# Main_Board.net
KiCad netlist of a schematic drawn in Altium Designer
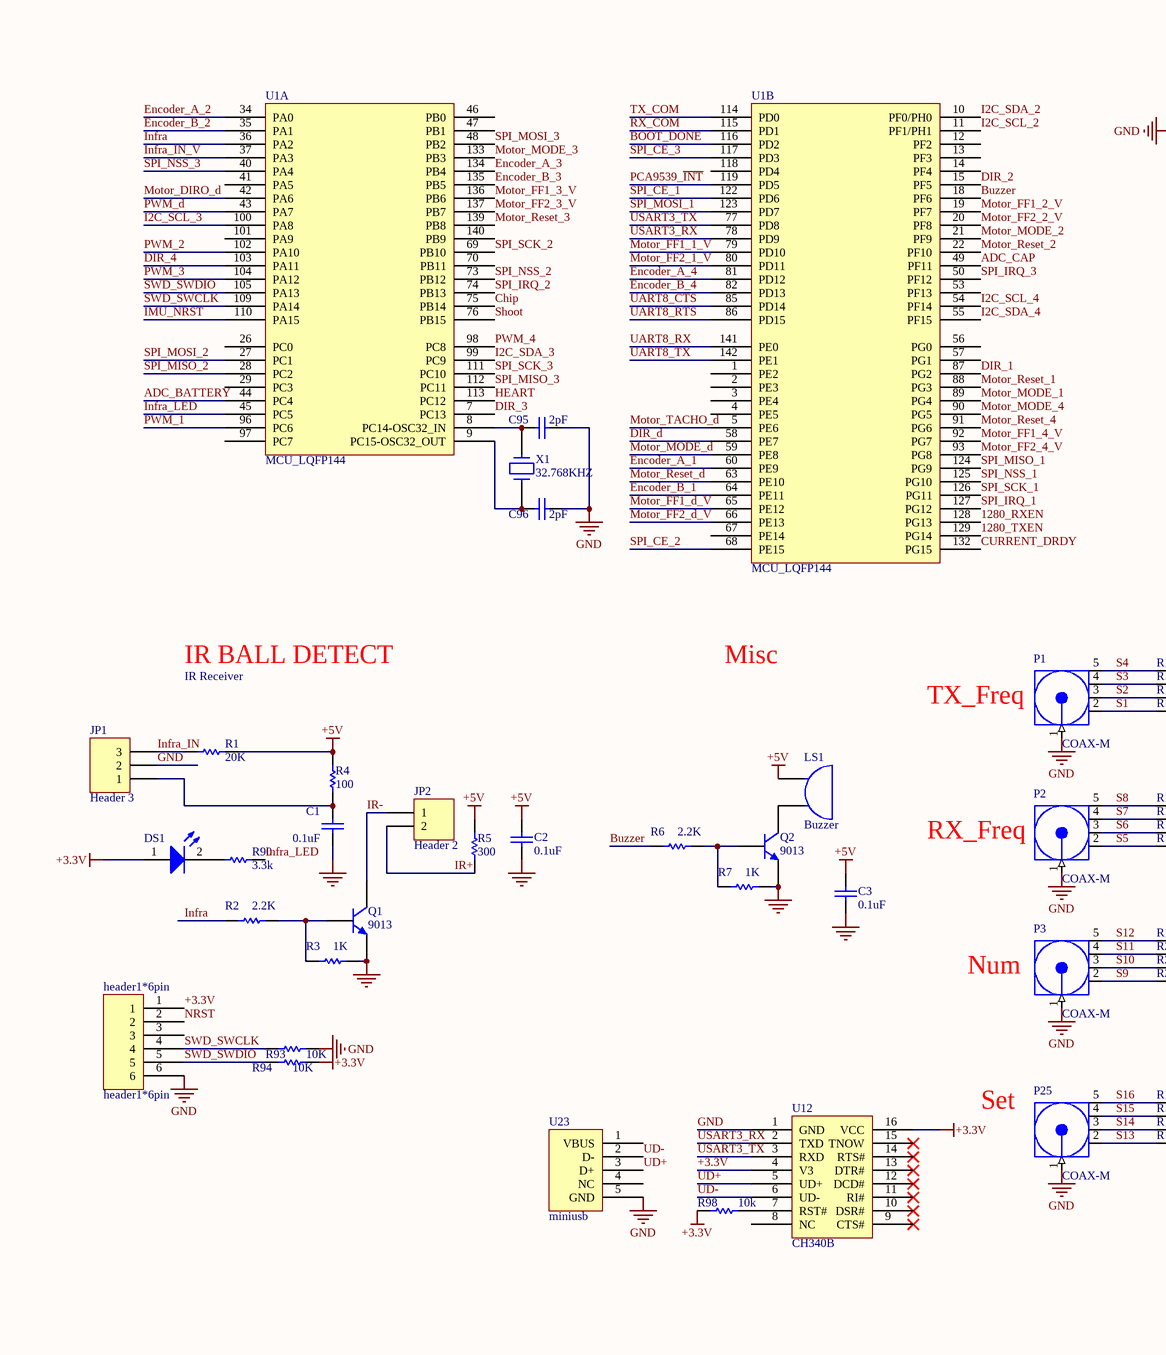
[diagram p0: Main_Board.SchDoc, left]
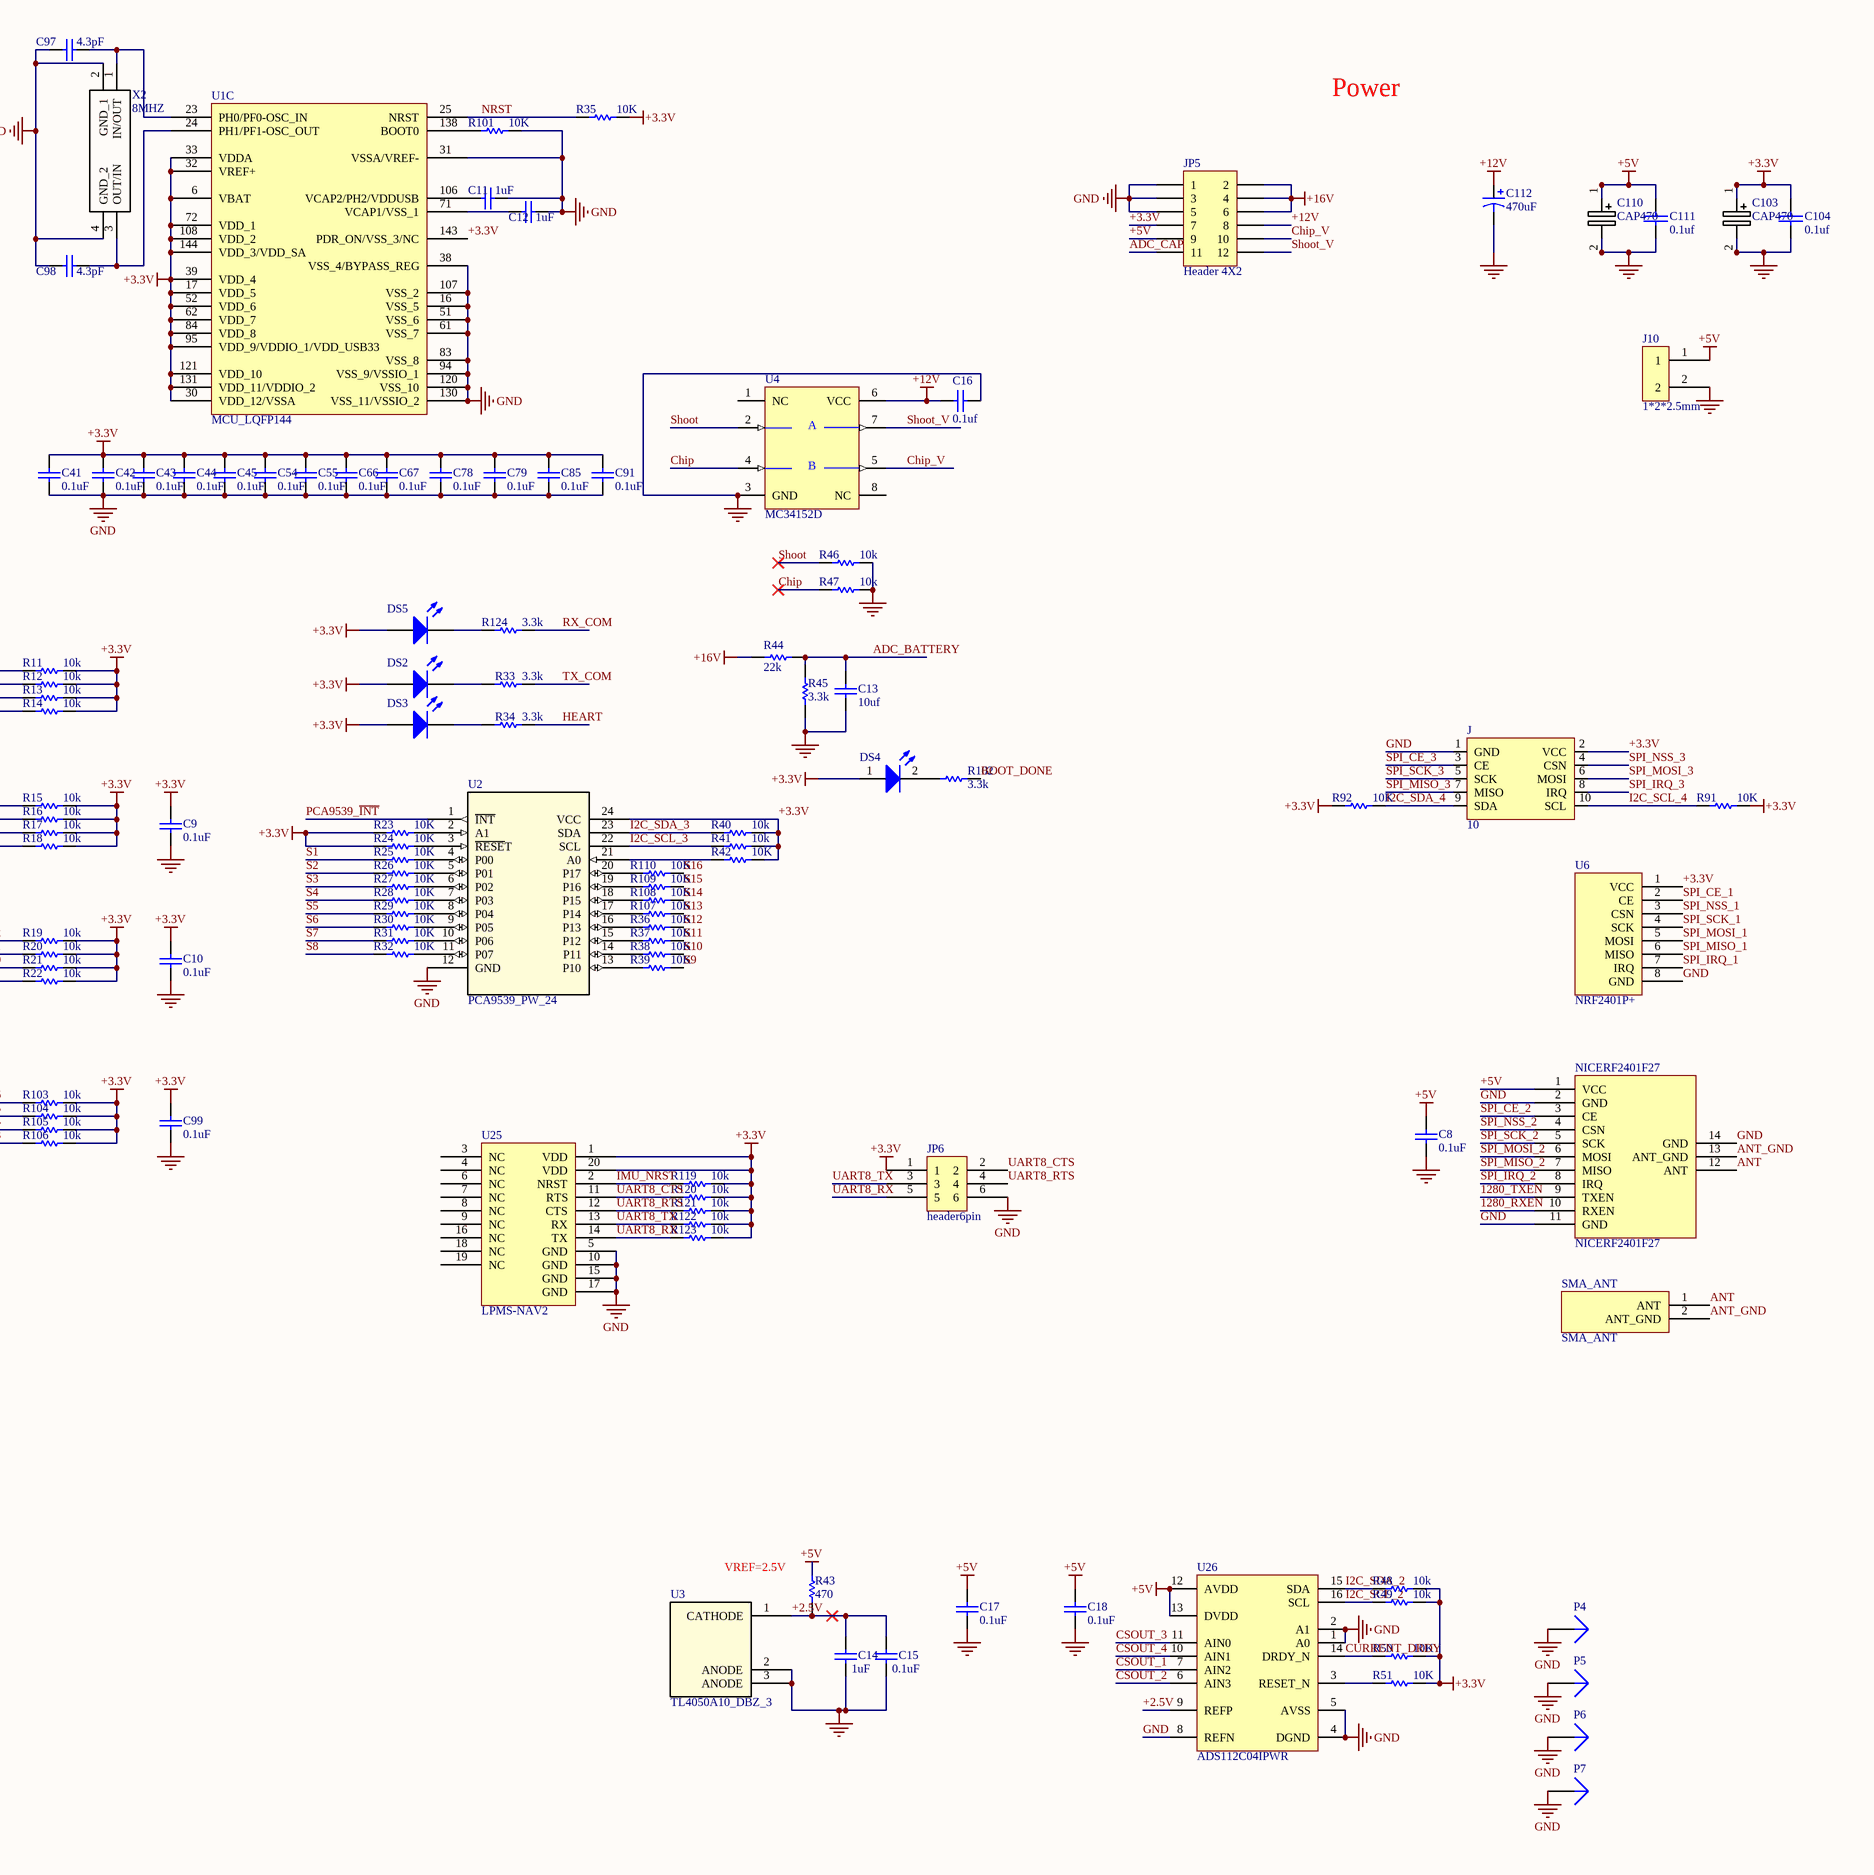
[diagram p1: Main_Board.SchDoc, right]

(export (version "E")
  (design (tool "Eeschema 10.0.6"))
  (components
    (comp (ref "C1")
      (value "0.1uF")
      (footprint "0805C")
      (description "Capacitor")
      (fields (field (name "Comment") "0.1uf") (field (name "PUBLISHER") "Altium Limited"))
      (libsource (lib "Miscellaneous Devices") (part "Cap"))
    )
    (comp (ref "C2")
      (value "0.1uF")
      (footprint "0805C")
      (description "Capacitor")
      (fields (field (name "Comment") "0.1uf") (field (name "PUBLISHER") "Altium Limited"))
      (libsource (lib "Miscellaneous Devices") (part "Cap"))
    )
    (comp (ref "C3")
      (value "0.1uF")
      (footprint "0805C")
      (description "Capacitor")
      (fields (field (name "Comment") "0.1uf") (field (name "PUBLISHER") "Altium Limited"))
      (libsource (lib "Miscellaneous Devices") (part "Cap"))
    )
    (comp (ref "C8")
      (value "0.1uF")
      (footprint "0805C")
      (description "Capacitor")
      (fields (field (name "PUBLISHER") "Altium Limited"))
      (libsource (lib "Miscellaneous Devices") (part "Cap"))
    )
    (comp (ref "C9")
      (value "0.1uF")
      (footprint "0805C")
      (description "Capacitor")
      (fields (field (name "Comment") "0.1uf") (field (name "PUBLISHER") "Altium Limited"))
      (libsource (lib "Miscellaneous Devices") (part "Cap"))
    )
    (comp (ref "C10")
      (value "0.1uF")
      (footprint "0805C")
      (description "Capacitor")
      (fields (field (name "Comment") "0.1uf") (field (name "PUBLISHER") "Altium Limited"))
      (libsource (lib "Miscellaneous Devices") (part "Cap"))
    )
    (comp (ref "C11")
      (value "1uF")
      (footprint "0805C")
      (description "Capacitor")
      (fields (field (name "Comment") "1uf") (field (name "PUBLISHER") "Altium Limited"))
      (libsource (lib "Miscellaneous Devices") (part "Cap"))
    )
    (comp (ref "C12")
      (value "1uF")
      (footprint "0805C")
      (description "Capacitor")
      (fields (field (name "Comment") "1uf") (field (name "PUBLISHER") "Altium Limited"))
      (libsource (lib "Miscellaneous Devices") (part "Cap"))
    )
    (comp (ref "C13")
      (value "10uf")
      (footprint "0805C")
      (description "Capacitor")
      (fields (field (name "PUBLISHER") "Altium Limited"))
      (libsource (lib "Miscellaneous Devices") (part "Cap"))
    )
    (comp (ref "C14")
      (value "1uF")
      (footprint "0805C")
      (description "Capacitor")
      (fields
        (field (name "MANUFACTURER") "Generic Components")
        (field (name "Comment") "1uf")
        (field (name "PUBLISHER") "Altium Hobart Technology Centre")
      )
      (libsource (lib "Miscellaneous Devices") (part "Cap"))
    )
    (comp (ref "C15")
      (value "0.1uF")
      (footprint "0805C")
      (description "Capacitor")
      (fields
        (field (name "MANUFACTURER") "Generic Components")
        (field (name "Comment") "0.1uf")
        (field (name "PUBLISHER") "Altium Hobart Technology Centre")
      )
      (libsource (lib "Miscellaneous Devices") (part "Cap"))
    )
    (comp (ref "C16")
      (value "0.1uf")
      (footprint "0805C")
      (description "Capacitor")
      (fields (field (name "PUBLISHER") "Altium Limited"))
      (libsource (lib "Miscellaneous Devices") (part "Cap"))
    )
    (comp (ref "C17")
      (value "0.1uF")
      (footprint "0805C")
      (description "Capacitor")
      (fields
        (field (name "MANUFACTURER") "Generic Components")
        (field (name "Comment") "0.1uf")
        (field (name "PUBLISHER") "Altium Hobart Technology Centre")
      )
      (libsource (lib "Miscellaneous Devices") (part "Cap"))
    )
    (comp (ref "C18")
      (value "0.1uF")
      (footprint "0805C")
      (description "Capacitor")
      (fields
        (field (name "MANUFACTURER") "Generic Components")
        (field (name "Comment") "0.1uf")
        (field (name "PUBLISHER") "Altium Hobart Technology Centre")
      )
      (libsource (lib "Miscellaneous Devices") (part "Cap"))
    )
    (comp (ref "C41")
      (value "0.1uF")
      (footprint "0805C")
      (description "Capacitor")
      (fields (field (name "PUBLISHER") "Altium Limited"))
      (libsource (lib "Miscellaneous Devices") (part "Cap"))
    )
    (comp (ref "C42")
      (value "0.1uF")
      (footprint "0805C")
      (description "Capacitor")
      (fields (field (name "Comment") "0.1uf") (field (name "PUBLISHER") "Altium Limited"))
      (libsource (lib "Miscellaneous Devices") (part "Cap"))
    )
    (comp (ref "C43")
      (value "0.1uF")
      (footprint "0805C")
      (description "Capacitor")
      (fields (field (name "Comment") "0.1uf") (field (name "PUBLISHER") "Altium Limited"))
      (libsource (lib "Miscellaneous Devices") (part "Cap"))
    )
    (comp (ref "C44")
      (value "0.1uF")
      (footprint "0805C")
      (description "Capacitor")
      (fields (field (name "Comment") "0.1uf") (field (name "PUBLISHER") "Altium Limited"))
      (libsource (lib "Miscellaneous Devices") (part "Cap"))
    )
    (comp (ref "C45")
      (value "0.1uF")
      (footprint "0805C")
      (description "Capacitor")
      (fields (field (name "Comment") "0.1uf") (field (name "PUBLISHER") "Altium Limited"))
      (libsource (lib "Miscellaneous Devices") (part "Cap"))
    )
    (comp (ref "C54")
      (value "0.1uF")
      (footprint "0805C")
      (description "Capacitor")
      (fields (field (name "Comment") "0.1uf") (field (name "PUBLISHER") "Altium Limited"))
      (libsource (lib "Miscellaneous Devices") (part "Cap"))
    )
    (comp (ref "C55")
      (value "0.1uF")
      (footprint "0805C")
      (description "Capacitor")
      (fields (field (name "Comment") "0.1uf") (field (name "PUBLISHER") "Altium Limited"))
      (libsource (lib "Miscellaneous Devices") (part "Cap"))
    )
    (comp (ref "C66")
      (value "0.1uF")
      (footprint "0805C")
      (description "Capacitor")
      (fields (field (name "Comment") "0.1uf") (field (name "PUBLISHER") "Altium Limited"))
      (libsource (lib "Miscellaneous Devices") (part "Cap"))
    )
    (comp (ref "C67")
      (value "0.1uF")
      (footprint "0805C")
      (description "Capacitor")
      (fields (field (name "Comment") "0.1uf") (field (name "PUBLISHER") "Altium Limited"))
      (libsource (lib "Miscellaneous Devices") (part "Cap"))
    )
    (comp (ref "C78")
      (value "0.1uF")
      (footprint "0805C")
      (description "Capacitor")
      (fields (field (name "Comment") "0.1uf") (field (name "PUBLISHER") "Altium Limited"))
      (libsource (lib "Miscellaneous Devices") (part "Cap"))
    )
    (comp (ref "C79")
      (value "0.1uF")
      (footprint "0805C")
      (description "Capacitor")
      (fields (field (name "Comment") "0.1uf") (field (name "PUBLISHER") "Altium Limited"))
      (libsource (lib "Miscellaneous Devices") (part "Cap"))
    )
    (comp (ref "C85")
      (value "0.1uF")
      (footprint "0805C")
      (description "Capacitor")
      (fields (field (name "Comment") "0.1uf") (field (name "PUBLISHER") "Altium Limited"))
      (libsource (lib "Miscellaneous Devices") (part "Cap"))
    )
    (comp (ref "C91")
      (value "0.1uF")
      (footprint "0805C")
      (description "Capacitor")
      (fields (field (name "Comment") "0.1uf") (field (name "PUBLISHER") "Altium Limited"))
      (libsource (lib "Miscellaneous Devices") (part "Cap"))
    )
    (comp (ref "C95")
      (value "2pF")
      (footprint "0805C")
      (description "Capacitor")
      (fields (field (name "Comment") "2pf") (field (name "PUBLISHER") "Altium Limited"))
      (libsource (lib "Miscellaneous Devices") (part "Cap"))
    )
    (comp (ref "C96")
      (value "2pF")
      (footprint "0805C")
      (description "Capacitor")
      (fields (field (name "Comment") "2pf") (field (name "PUBLISHER") "Altium Limited"))
      (libsource (lib "Miscellaneous Devices") (part "Cap"))
    )
    (comp (ref "C97")
      (value "4.3pF")
      (footprint "0805C")
      (description "Capacitor")
      (fields (field (name "Comment") "4.3pf") (field (name "PUBLISHER") "Altium Limited"))
      (libsource (lib "Miscellaneous Devices") (part "Cap"))
    )
    (comp (ref "C98")
      (value "4.3pF")
      (footprint "0805C")
      (description "Capacitor")
      (fields (field (name "Comment") "4.3pf") (field (name "PUBLISHER") "Altium Limited"))
      (libsource (lib "Miscellaneous Devices") (part "Cap"))
    )
    (comp (ref "C99")
      (value "0.1uF")
      (footprint "0805C")
      (description "Capacitor")
      (fields (field (name "PUBLISHER") "Altium Limited"))
      (libsource (lib "Miscellaneous Devices") (part "Cap"))
    )
    (comp (ref "C103")
      (value "CAP470")
      (footprint "Main_Board:CAPPM7360X200N")
      (description "470uF电容贴片")
      (fields
        (field (name "MANUFACTURER_PART_NUMBER") "T523H477M016APE0707280")
        (field (name "MOUSER PART NUMBER") "80-T523H477M16P070LR")
      )
      (libsource (lib "Main_Board") (part "T523H477M016APE0707280"))
    )
    (comp (ref "C104")
      (value "0.1uf")
      (footprint "0805C")
      (description "Capacitor")
      (libsource (lib "*") (part "CAP"))
    )
    (comp (ref "C110")
      (value "CAP470")
      (footprint "Main_Board:CAPPM7360X200N")
      (description "470uF电容贴片")
      (fields
        (field (name "MANUFACTURER_PART_NUMBER") "T523H477M016APE0707280")
        (field (name "MOUSER PART NUMBER") "80-T523H477M16P070LR")
      )
      (libsource (lib "Main_Board") (part "T523H477M016APE0707280"))
    )
    (comp (ref "C111")
      (value "0.1uf")
      (footprint "0805C")
      (description "Capacitor")
      (libsource (lib "*") (part "CAP"))
    )
    (comp (ref "C112")
      (value "470uF")
      (footprint "470uF")
      (description "Polarized Capacitor (Radial)")
      (fields (field (name "PUBLISHER") "Altium Limited"))
      (libsource (lib "Miscellaneous Devices") (part "Cap Pol1"))
    )
    (comp (ref "DS1")
      (value "LED2")
      (footprint "0805D")
      (description "Typical RED, GREEN, YELLOW, AMBER GaAs LED")
      (fields
        (field (name "MANUFACTURER") "Generic Components")
        (field (name "PUBLISHER") "Altium Hobart Technology Centre")
      )
      (libsource (lib "Miscellaneous Devices") (part "LED2"))
    )
    (comp (ref "DS2")
      (value "LED1")
      (footprint "0805D")
      (description "Typical RED, GREEN, YELLOW, AMBER GaAs LED")
      (fields (field (name "PUBLISHER") "Altium Limited"))
      (libsource (lib "Miscellaneous Devices") (part "LED1"))
    )
    (comp (ref "DS3")
      (value "LED2")
      (footprint "0805D")
      (description "Typical RED, GREEN, YELLOW, AMBER GaAs LED")
      (fields (field (name "PUBLISHER") "Altium Limited"))
      (libsource (lib "") (part "LED2_1"))
    )
    (comp (ref "DS4")
      (value "LED2")
      (footprint "0805D")
      (description "Typical RED, GREEN, YELLOW, AMBER GaAs LED")
      (fields
        (field (name "MANUFACTURER") "Generic Components")
        (field (name "PUBLISHER") "Altium Hobart Technology Centre")
      )
      (libsource (lib "Miscellaneous Devices") (part "LED2"))
    )
    (comp (ref "DS5")
      (value "LED1")
      (footprint "0805D")
      (description "Typical RED, GREEN, YELLOW, AMBER GaAs LED")
      (fields (field (name "PUBLISHER") "Altium Limited"))
      (libsource (lib "Miscellaneous Devices") (part "LED1"))
    )
    (comp (ref "header1*6pin")
      (value "header1*6pin")
      (footprint "1*6_2.5mm")
      (libsource (lib "Main_Board") (part "header1*6pin"))
    )
    (comp (ref "J") (value "10") (footprint "Main_Board:10") (libsource (lib "Main_Board") (part "10")))
    (comp (ref "J10")
      (value "1*2*2.5mm")
      (footprint "1*2_2.5mm")
      (libsource (lib "Main_Board") (part "1*2*2.5mm"))
    )
    (comp (ref "JP1")
      (value "Header 3")
      (footprint "SHDR3")
      (description "Header, 3-Pin")
      (fields (field (name "PUBLISHER") "Altium Limited"))
      (libsource (lib "Miscellaneous Connectors") (part "Header 3"))
    )
    (comp (ref "JP2")
      (value "Header 2")
      (footprint "SHDR2")
      (description "Header, 2-Pin")
      (fields (field (name "PUBLISHER") "Altium Limited"))
      (libsource (lib "Miscellaneous Connectors") (part "Header 2"))
    )
    (comp (ref "JP5")
      (value "Header 4X2")
      (footprint "2*6_2.5mm")
      (description "Header, 4-Pin, Dual row")
      (fields (field (name "PUBLISHER") "Altium Limited"))
      (libsource (lib "booster") (part "Header 6X2"))
    )
    (comp (ref "JP6")
      (value "header6pin")
      (footprint "2*3_2.5mm")
      (libsource (lib "Main_Board") (part "header6pin"))
    )
    (comp (ref "LS1")
      (value "Buzzer")
      (footprint "Buzzer")
      (fields (field (name "MANUFACTURER") "Generic Components"))
      (libsource (lib "Miscellaneous Devices") (part "Buzzer"))
    )
    (comp (ref "NICERF2401F27")
      (value "NICERF2401F27")
      (footprint "NICERF2401F27")
      (libsource (lib "Main_Board") (part "NICERF2401F27"))
    )
    (comp (ref "P1")
      (value "COAX-M")
      (footprint "A6RV-161RS")
      (description "RF Coaxial PCB Connector, MMCX; Thru-Hole, Vertical Mount Plug,  50 Ohm Impedance")
      (fields (field (name "PUBLISHER") "Altium Limited"))
      (libsource (lib "Miscellaneous Connectors") (part "COAX-M"))
    )
    (comp (ref "P2")
      (value "COAX-M")
      (footprint "A6RV-161RS")
      (description "RF Coaxial PCB Connector, MMCX; Thru-Hole, Vertical Mount Plug,  50 Ohm Impedance")
      (fields (field (name "PUBLISHER") "Altium Limited"))
      (libsource (lib "Miscellaneous Connectors") (part "COAX-M"))
    )
    (comp (ref "P3")
      (value "COAX-M")
      (footprint "A6RV-161RS")
      (description "RF Coaxial PCB Connector, MMCX; Thru-Hole, Vertical Mount Plug,  50 Ohm Impedance")
      (fields (field (name "PUBLISHER") "Altium Limited"))
      (libsource (lib "Miscellaneous Connectors") (part "COAX-M"))
    )
    (comp (ref "P4")
      (value "安装孔")
      (footprint "安装孔-3.5-5")
      (description "Plug")
      (fields (field (name "PUBLISHER") "Altium Limited"))
      (libsource (lib "Miscellaneous Connectors") (part "Plug"))
    )
    (comp (ref "P5")
      (value "安装孔")
      (footprint "安装孔-3.5-5")
      (description "Plug")
      (fields (field (name "PUBLISHER") "Altium Limited"))
      (libsource (lib "Miscellaneous Connectors") (part "Plug"))
    )
    (comp (ref "P6")
      (value "安装孔")
      (footprint "安装孔-3.5-5")
      (description "Plug")
      (fields (field (name "PUBLISHER") "Altium Limited"))
      (libsource (lib "Miscellaneous Connectors") (part "Plug"))
    )
    (comp (ref "P7")
      (value "安装孔")
      (footprint "安装孔-3.5-5")
      (description "Plug")
      (fields (field (name "PUBLISHER") "Altium Limited"))
      (libsource (lib "Miscellaneous Connectors") (part "Plug"))
    )
    (comp (ref "P25")
      (value "COAX-M")
      (footprint "A6RV-161RS")
      (description "RF Coaxial PCB Connector, MMCX; Thru-Hole, Vertical Mount Plug,  50 Ohm Impedance")
      (fields (field (name "PUBLISHER") "Altium Limited"))
      (libsource (lib "Miscellaneous Connectors") (part "COAX-M"))
    )
    (comp (ref "Q1")
      (value "9013")
      (footprint "SO-G3/Y1")
      (description "NPN General Purpose Amplifier")
      (fields
        (field (name "MANUFACTURER") "Fairchild Semiconductor")
        (field (name "PUBLISHER") "Altium Hobart Technology Centre")
      )
      (libsource (lib "FSC Discrete BJT") (part "BC817-40"))
    )
    (comp (ref "Q2")
      (value "9013")
      (footprint "SO-G3/Y1")
      (description "NPN General Purpose Amplifier")
      (fields
        (field (name "MANUFACTURER") "Fairchild Semiconductor")
        (field (name "PUBLISHER") "Altium Hobart Technology Centre")
      )
      (libsource (lib "FSC Discrete BJT") (part "BC817-40"))
    )
    (comp (ref "R1")
      (value "20K")
      (footprint "0805R")
      (description "Resistor")
      (fields
        (field (name "MANUFACTURER") "Generic Components")
        (field (name "Comment") "20k")
        (field (name "PUBLISHER") "Altium Hobart Technology Centre")
      )
      (libsource (lib "Miscellaneous Devices") (part "Res1"))
    )
    (comp (ref "R2")
      (value "2.2K")
      (footprint "0805R")
      (description "Resistor")
      (fields
        (field (name "MANUFACTURER") "Generic Components")
        (field (name "Comment") "2.2k")
        (field (name "PUBLISHER") "Altium Hobart Technology Centre")
      )
      (libsource (lib "Miscellaneous Devices") (part "Res1"))
    )
    (comp (ref "R3")
      (value "1K")
      (footprint "0805R")
      (description "Resistor")
      (fields
        (field (name "MANUFACTURER") "Generic Components")
        (field (name "Comment") "1k")
        (field (name "PUBLISHER") "Altium Hobart Technology Centre")
      )
      (libsource (lib "Miscellaneous Devices") (part "Res1"))
    )
    (comp (ref "R4")
      (value "100")
      (footprint "0805R")
      (description "Resistor")
      (fields
        (field (name "MANUFACTURER") "Generic Components")
        (field (name "PUBLISHER") "Altium Hobart Technology Centre")
      )
      (libsource (lib "Miscellaneous Devices") (part "Res1"))
    )
    (comp (ref "R5")
      (value "300")
      (footprint "0805R")
      (description "Resistor")
      (fields
        (field (name "MANUFACTURER") "Generic Components")
        (field (name "PUBLISHER") "Altium Hobart Technology Centre")
      )
      (libsource (lib "Miscellaneous Devices") (part "Res1"))
    )
    (comp (ref "R6")
      (value "2.2K")
      (footprint "0805R")
      (description "Resistor")
      (fields
        (field (name "MANUFACTURER") "Generic Components")
        (field (name "Comment") "2.2k")
        (field (name "PUBLISHER") "Altium Hobart Technology Centre")
      )
      (libsource (lib "Miscellaneous Devices") (part "Res1"))
    )
    (comp (ref "R7")
      (value "1K")
      (footprint "0805R")
      (description "Resistor")
      (fields
        (field (name "MANUFACTURER") "Generic Components")
        (field (name "Comment") "1k")
        (field (name "PUBLISHER") "Altium Hobart Technology Centre")
      )
      (libsource (lib "Miscellaneous Devices") (part "Res1"))
    )
    (comp (ref "R11")
      (value "10k")
      (footprint "0805R")
      (description "Resistor")
      (fields
        (field (name "MANUFACTURER") "Generic Components")
        (field (name "PUBLISHER") "Altium Hobart Technology Centre")
      )
      (libsource (lib "Miscellaneous Devices") (part "Res1"))
    )
    (comp (ref "R12")
      (value "10k")
      (footprint "0805R")
      (description "Resistor")
      (fields
        (field (name "MANUFACTURER") "Generic Components")
        (field (name "PUBLISHER") "Altium Hobart Technology Centre")
      )
      (libsource (lib "Miscellaneous Devices") (part "Res1"))
    )
    (comp (ref "R13")
      (value "10k")
      (footprint "0805R")
      (description "Resistor")
      (fields
        (field (name "MANUFACTURER") "Generic Components")
        (field (name "PUBLISHER") "Altium Hobart Technology Centre")
      )
      (libsource (lib "Miscellaneous Devices") (part "Res1"))
    )
    (comp (ref "R14")
      (value "10k")
      (footprint "0805R")
      (description "Resistor")
      (fields
        (field (name "MANUFACTURER") "Generic Components")
        (field (name "PUBLISHER") "Altium Hobart Technology Centre")
      )
      (libsource (lib "Miscellaneous Devices") (part "Res1"))
    )
    (comp (ref "R15")
      (value "10k")
      (footprint "0805R")
      (description "Resistor")
      (fields
        (field (name "MANUFACTURER") "Generic Components")
        (field (name "PUBLISHER") "Altium Hobart Technology Centre")
      )
      (libsource (lib "Miscellaneous Devices") (part "Res1"))
    )
    (comp (ref "R16")
      (value "10k")
      (footprint "0805R")
      (description "Resistor")
      (fields
        (field (name "MANUFACTURER") "Generic Components")
        (field (name "PUBLISHER") "Altium Hobart Technology Centre")
      )
      (libsource (lib "Miscellaneous Devices") (part "Res1"))
    )
    (comp (ref "R17")
      (value "10k")
      (footprint "0805R")
      (description "Resistor")
      (fields
        (field (name "MANUFACTURER") "Generic Components")
        (field (name "PUBLISHER") "Altium Hobart Technology Centre")
      )
      (libsource (lib "Miscellaneous Devices") (part "Res1"))
    )
    (comp (ref "R18")
      (value "10k")
      (footprint "0805R")
      (description "Resistor")
      (fields
        (field (name "MANUFACTURER") "Generic Components")
        (field (name "PUBLISHER") "Altium Hobart Technology Centre")
      )
      (libsource (lib "Miscellaneous Devices") (part "Res1"))
    )
    (comp (ref "R19")
      (value "10k")
      (footprint "0805R")
      (description "Resistor")
      (fields
        (field (name "MANUFACTURER") "Generic Components")
        (field (name "PUBLISHER") "Altium Hobart Technology Centre")
      )
      (libsource (lib "Miscellaneous Devices") (part "Res1"))
    )
    (comp (ref "R20")
      (value "10k")
      (footprint "0805R")
      (description "Resistor")
      (fields
        (field (name "MANUFACTURER") "Generic Components")
        (field (name "PUBLISHER") "Altium Hobart Technology Centre")
      )
      (libsource (lib "Miscellaneous Devices") (part "Res1"))
    )
    (comp (ref "R21")
      (value "10k")
      (footprint "0805R")
      (description "Resistor")
      (fields
        (field (name "MANUFACTURER") "Generic Components")
        (field (name "PUBLISHER") "Altium Hobart Technology Centre")
      )
      (libsource (lib "Miscellaneous Devices") (part "Res1"))
    )
    (comp (ref "R22")
      (value "10k")
      (footprint "0805R")
      (description "Resistor")
      (fields
        (field (name "MANUFACTURER") "Generic Components")
        (field (name "PUBLISHER") "Altium Hobart Technology Centre")
      )
      (libsource (lib "Miscellaneous Devices") (part "Res1"))
    )
    (comp (ref "R23")
      (value "10K")
      (footprint "0805R")
      (description "Resistor")
      (fields
        (field (name "MANUFACTURER") "Generic Components")
        (field (name "Comment") "10k")
        (field (name "PUBLISHER") "Altium Hobart Technology Centre")
      )
      (libsource (lib "Miscellaneous Devices") (part "Res1"))
    )
    (comp (ref "R24")
      (value "10K")
      (footprint "0805R")
      (description "Resistor")
      (fields
        (field (name "MANUFACTURER") "Generic Components")
        (field (name "Comment") "10k")
        (field (name "PUBLISHER") "Altium Hobart Technology Centre")
      )
      (libsource (lib "Miscellaneous Devices") (part "Res1"))
    )
    (comp (ref "R25")
      (value "10K")
      (footprint "0805R")
      (description "Resistor")
      (fields
        (field (name "MANUFACTURER") "Generic Components")
        (field (name "Comment") "10k")
        (field (name "PUBLISHER") "Altium Hobart Technology Centre")
      )
      (libsource (lib "Miscellaneous Devices") (part "Res1"))
    )
    (comp (ref "R26")
      (value "10K")
      (footprint "0805R")
      (description "Resistor")
      (fields
        (field (name "MANUFACTURER") "Generic Components")
        (field (name "Comment") "10k")
        (field (name "PUBLISHER") "Altium Hobart Technology Centre")
      )
      (libsource (lib "Miscellaneous Devices") (part "Res1"))
    )
    (comp (ref "R27")
      (value "10K")
      (footprint "0805R")
      (description "Resistor")
      (fields
        (field (name "MANUFACTURER") "Generic Components")
        (field (name "Comment") "10k")
        (field (name "PUBLISHER") "Altium Hobart Technology Centre")
      )
      (libsource (lib "Miscellaneous Devices") (part "Res1"))
    )
    (comp (ref "R28")
      (value "10K")
      (footprint "0805R")
      (description "Resistor")
      (fields
        (field (name "MANUFACTURER") "Generic Components")
        (field (name "Comment") "10k")
        (field (name "PUBLISHER") "Altium Hobart Technology Centre")
      )
      (libsource (lib "Miscellaneous Devices") (part "Res1"))
    )
    (comp (ref "R29")
      (value "10K")
      (footprint "0805R")
      (description "Resistor")
      (fields
        (field (name "MANUFACTURER") "Generic Components")
        (field (name "Comment") "10k")
        (field (name "PUBLISHER") "Altium Hobart Technology Centre")
      )
      (libsource (lib "Miscellaneous Devices") (part "Res1"))
    )
    (comp (ref "R30")
      (value "10K")
      (footprint "0805R")
      (description "Resistor")
      (fields
        (field (name "MANUFACTURER") "Generic Components")
        (field (name "Comment") "10k")
        (field (name "PUBLISHER") "Altium Hobart Technology Centre")
      )
      (libsource (lib "Miscellaneous Devices") (part "Res1"))
    )
    (comp (ref "R31")
      (value "10K")
      (footprint "0805R")
      (description "Resistor")
      (fields
        (field (name "MANUFACTURER") "Generic Components")
        (field (name "Comment") "10k")
        (field (name "PUBLISHER") "Altium Hobart Technology Centre")
      )
      (libsource (lib "Miscellaneous Devices") (part "Res1"))
    )
    (comp (ref "R32")
      (value "10K")
      (footprint "0805R")
      (description "Resistor")
      (fields
        (field (name "MANUFACTURER") "Generic Components")
        (field (name "Comment") "10k")
        (field (name "PUBLISHER") "Altium Hobart Technology Centre")
      )
      (libsource (lib "Miscellaneous Devices") (part "Res1"))
    )
    (comp (ref "R33")
      (value "3.3k")
      (footprint "0805R")
      (description "Resistor")
      (fields
        (field (name "MANUFACTURER") "Generic Components")
        (field (name "PUBLISHER") "Altium Hobart Technology Centre")
      )
      (libsource (lib "Miscellaneous Devices") (part "Res1"))
    )
    (comp (ref "R34")
      (value "3.3k")
      (footprint "0805R")
      (description "Resistor")
      (fields
        (field (name "MANUFACTURER") "Generic Components")
        (field (name "PUBLISHER") "Altium Hobart Technology Centre")
      )
      (libsource (lib "Miscellaneous Devices") (part "Res1"))
    )
    (comp (ref "R35")
      (value "10K")
      (footprint "0805R")
      (description "Resistor")
      (fields
        (field (name "MANUFACTURER") "Generic Components")
        (field (name "Comment") "10k")
        (field (name "PUBLISHER") "Altium Hobart Technology Centre")
      )
      (libsource (lib "Miscellaneous Devices") (part "Res1"))
    )
    (comp (ref "R36")
      (value "10K")
      (footprint "0805R")
      (description "Resistor")
      (fields
        (field (name "MANUFACTURER") "Generic Components")
        (field (name "Comment") "10k")
        (field (name "PUBLISHER") "Altium Hobart Technology Centre")
      )
      (libsource (lib "Miscellaneous Devices") (part "Res1"))
    )
    (comp (ref "R37")
      (value "10K")
      (footprint "0805R")
      (description "Resistor")
      (fields
        (field (name "MANUFACTURER") "Generic Components")
        (field (name "Comment") "10k")
        (field (name "PUBLISHER") "Altium Hobart Technology Centre")
      )
      (libsource (lib "Miscellaneous Devices") (part "Res1"))
    )
    (comp (ref "R38")
      (value "10K")
      (footprint "0805R")
      (description "Resistor")
      (fields
        (field (name "MANUFACTURER") "Generic Components")
        (field (name "Comment") "10k")
        (field (name "PUBLISHER") "Altium Hobart Technology Centre")
      )
      (libsource (lib "Miscellaneous Devices") (part "Res1"))
    )
    (comp (ref "R39")
      (value "10K")
      (footprint "0805R")
      (description "Resistor")
      (fields
        (field (name "MANUFACTURER") "Generic Components")
        (field (name "Comment") "10k")
        (field (name "PUBLISHER") "Altium Hobart Technology Centre")
      )
      (libsource (lib "Miscellaneous Devices") (part "Res1"))
    )
    (comp (ref "R40")
      (value "10k")
      (footprint "0805R")
      (description "Resistor")
      (fields
        (field (name "MANUFACTURER") "Generic Components")
        (field (name "PUBLISHER") "Altium Hobart Technology Centre")
      )
      (libsource (lib "Miscellaneous Devices") (part "Res1"))
    )
    (comp (ref "R41")
      (value "10k")
      (footprint "0805R")
      (description "Resistor")
      (fields
        (field (name "MANUFACTURER") "Generic Components")
        (field (name "PUBLISHER") "Altium Hobart Technology Centre")
      )
      (libsource (lib "Miscellaneous Devices") (part "Res1"))
    )
    (comp (ref "R42")
      (value "10K")
      (footprint "0805R")
      (description "Resistor")
      (fields
        (field (name "MANUFACTURER") "Generic Components")
        (field (name "Comment") "10k")
        (field (name "PUBLISHER") "Altium Hobart Technology Centre")
      )
      (libsource (lib "Miscellaneous Devices") (part "Res1"))
    )
    (comp (ref "R43")
      (value "470")
      (footprint "0805R")
      (description "Resistor")
      (fields
        (field (name "MANUFACTURER") "Generic Components")
        (field (name "PUBLISHER") "Altium Hobart Technology Centre")
      )
      (libsource (lib "Miscellaneous Devices") (part "Res1"))
    )
    (comp (ref "R44")
      (value "22k")
      (footprint "0805R")
      (description "Resistor")
      (fields
        (field (name "MANUFACTURER") "Generic Components")
        (field (name "PUBLISHER") "Altium Hobart Technology Centre")
      )
      (libsource (lib "Miscellaneous Devices") (part "Res1"))
    )
    (comp (ref "R45")
      (value "3.3k")
      (footprint "0805R")
      (description "Resistor")
      (fields
        (field (name "MANUFACTURER") "Generic Components")
        (field (name "PUBLISHER") "Altium Hobart Technology Centre")
      )
      (libsource (lib "Miscellaneous Devices") (part "Res1"))
    )
    (comp (ref "R46")
      (value "10k")
      (footprint "0805R")
      (description "Resistance")
      (libsource (lib "SMALLSIZE") (part "SR0805"))
    )
    (comp (ref "R47")
      (value "10k")
      (footprint "0805R")
      (description "Resistance")
      (libsource (lib "SMALLSIZE") (part "SR0805"))
    )
    (comp (ref "R48")
      (value "10k")
      (footprint "0805R")
      (description "Resistor")
      (fields
        (field (name "MANUFACTURER") "Generic Components")
        (field (name "PUBLISHER") "Altium Hobart Technology Centre")
      )
      (libsource (lib "Miscellaneous Devices") (part "Res1"))
    )
    (comp (ref "R49")
      (value "10k")
      (footprint "0805R")
      (description "Resistor")
      (fields
        (field (name "MANUFACTURER") "Generic Components")
        (field (name "PUBLISHER") "Altium Hobart Technology Centre")
      )
      (libsource (lib "Miscellaneous Devices") (part "Res1"))
    )
    (comp (ref "R50")
      (value "10K")
      (footprint "0805R")
      (description "Resistor")
      (fields
        (field (name "MANUFACTURER") "Generic Components")
        (field (name "Comment") "10k")
        (field (name "PUBLISHER") "Altium Hobart Technology Centre")
      )
      (libsource (lib "Miscellaneous Devices") (part "Res1"))
    )
    (comp (ref "R51")
      (value "10K")
      (footprint "0805R")
      (description "Resistor")
      (fields
        (field (name "MANUFACTURER") "Generic Components")
        (field (name "Comment") "10k")
        (field (name "PUBLISHER") "Altium Hobart Technology Centre")
      )
      (libsource (lib "Miscellaneous Devices") (part "Res1"))
    )
    (comp (ref "R90")
      (value "3.3k")
      (footprint "0805R")
      (description "Resistor")
      (fields
        (field (name "MANUFACTURER") "Generic Components")
        (field (name "PUBLISHER") "Altium Hobart Technology Centre")
      )
      (libsource (lib "Miscellaneous Devices") (part "Res1"))
    )
    (comp (ref "R91")
      (value "10K")
      (footprint "0805R")
      (description "Resistor")
      (fields
        (field (name "MANUFACTURER") "Generic Components")
        (field (name "Comment") "10k")
        (field (name "PUBLISHER") "Altium Hobart Technology Centre")
      )
      (libsource (lib "Miscellaneous Devices") (part "Res1"))
    )
    (comp (ref "R92")
      (value "10K")
      (footprint "0805R")
      (description "Resistor")
      (fields
        (field (name "MANUFACTURER") "Generic Components")
        (field (name "Comment") "10k")
        (field (name "PUBLISHER") "Altium Hobart Technology Centre")
      )
      (libsource (lib "Miscellaneous Devices") (part "Res1"))
    )
    (comp (ref "R93")
      (value "10K")
      (footprint "0805R")
      (description "Resistor")
      (fields
        (field (name "MANUFACTURER") "Generic Components")
        (field (name "Comment") "10k")
        (field (name "PUBLISHER") "Altium Hobart Technology Centre")
      )
      (libsource (lib "Miscellaneous Devices") (part "Res1"))
    )
    (comp (ref "R94")
      (value "10K")
      (footprint "0805R")
      (description "Resistor")
      (fields
        (field (name "MANUFACTURER") "Generic Components")
        (field (name "Comment") "10k")
        (field (name "PUBLISHER") "Altium Hobart Technology Centre")
      )
      (libsource (lib "Miscellaneous Devices") (part "Res1"))
    )
    (comp (ref "R98")
      (value "10k")
      (footprint "0805R")
      (description "Resistor")
      (fields
        (field (name "MANUFACTURER") "Generic Components")
        (field (name "PUBLISHER") "Altium Hobart Technology Centre")
      )
      (libsource (lib "Miscellaneous Devices") (part "Res1"))
    )
    (comp (ref "R101")
      (value "10K")
      (footprint "0805R")
      (description "Resistor")
      (fields
        (field (name "MANUFACTURER") "Generic Components")
        (field (name "Comment") "10k")
        (field (name "PUBLISHER") "Altium Hobart Technology Centre")
      )
      (libsource (lib "Miscellaneous Devices") (part "Res1"))
    )
    (comp (ref "R102")
      (value "3.3k")
      (footprint "0805R")
      (description "Resistor")
      (fields
        (field (name "MANUFACTURER") "Generic Components")
        (field (name "PUBLISHER") "Altium Hobart Technology Centre")
      )
      (libsource (lib "Miscellaneous Devices") (part "Res1"))
    )
    (comp (ref "R103")
      (value "10k")
      (footprint "0805R")
      (description "Resistor")
      (fields
        (field (name "MANUFACTURER") "Generic Components")
        (field (name "PUBLISHER") "Altium Hobart Technology Centre")
      )
      (libsource (lib "Miscellaneous Devices") (part "Res1"))
    )
    (comp (ref "R104")
      (value "10k")
      (footprint "0805R")
      (description "Resistor")
      (fields
        (field (name "MANUFACTURER") "Generic Components")
        (field (name "PUBLISHER") "Altium Hobart Technology Centre")
      )
      (libsource (lib "Miscellaneous Devices") (part "Res1"))
    )
    (comp (ref "R105")
      (value "10k")
      (footprint "0805R")
      (description "Resistor")
      (fields
        (field (name "MANUFACTURER") "Generic Components")
        (field (name "PUBLISHER") "Altium Hobart Technology Centre")
      )
      (libsource (lib "Miscellaneous Devices") (part "Res1"))
    )
    (comp (ref "R106")
      (value "10k")
      (footprint "0805R")
      (description "Resistor")
      (fields
        (field (name "MANUFACTURER") "Generic Components")
        (field (name "PUBLISHER") "Altium Hobart Technology Centre")
      )
      (libsource (lib "Miscellaneous Devices") (part "Res1"))
    )
    (comp (ref "R107")
      (value "10K")
      (footprint "0805R")
      (description "Resistor")
      (fields
        (field (name "MANUFACTURER") "Generic Components")
        (field (name "Comment") "10k")
        (field (name "PUBLISHER") "Altium Hobart Technology Centre")
      )
      (libsource (lib "Miscellaneous Devices") (part "Res1"))
    )
    (comp (ref "R108")
      (value "10K")
      (footprint "0805R")
      (description "Resistor")
      (fields
        (field (name "MANUFACTURER") "Generic Components")
        (field (name "Comment") "10k")
        (field (name "PUBLISHER") "Altium Hobart Technology Centre")
      )
      (libsource (lib "Miscellaneous Devices") (part "Res1"))
    )
    (comp (ref "R109")
      (value "10K")
      (footprint "0805R")
      (description "Resistor")
      (fields
        (field (name "MANUFACTURER") "Generic Components")
        (field (name "Comment") "10k")
        (field (name "PUBLISHER") "Altium Hobart Technology Centre")
      )
      (libsource (lib "Miscellaneous Devices") (part "Res1"))
    )
    (comp (ref "R110")
      (value "10K")
      (footprint "0805R")
      (description "Resistor")
      (fields
        (field (name "MANUFACTURER") "Generic Components")
        (field (name "Comment") "10k")
        (field (name "PUBLISHER") "Altium Hobart Technology Centre")
      )
      (libsource (lib "Miscellaneous Devices") (part "Res1"))
    )
    (comp (ref "R119")
      (value "10k")
      (footprint "0805R")
      (description "Resistor")
      (fields
        (field (name "MANUFACTURER") "Generic Components")
        (field (name "PUBLISHER") "Altium Hobart Technology Centre")
      )
      (libsource (lib "Miscellaneous Devices") (part "Res1"))
    )
    (comp (ref "R120")
      (value "10k")
      (footprint "0805R")
      (description "Resistor")
      (fields
        (field (name "MANUFACTURER") "Generic Components")
        (field (name "PUBLISHER") "Altium Hobart Technology Centre")
      )
      (libsource (lib "Miscellaneous Devices") (part "Res1"))
    )
    (comp (ref "R121")
      (value "10k")
      (footprint "0805R")
      (description "Resistor")
      (fields
        (field (name "MANUFACTURER") "Generic Components")
        (field (name "PUBLISHER") "Altium Hobart Technology Centre")
      )
      (libsource (lib "Miscellaneous Devices") (part "Res1"))
    )
    (comp (ref "R122")
      (value "10k")
      (footprint "0805R")
      (description "Resistor")
      (fields
        (field (name "MANUFACTURER") "Generic Components")
        (field (name "PUBLISHER") "Altium Hobart Technology Centre")
      )
      (libsource (lib "Miscellaneous Devices") (part "Res1"))
    )
    (comp (ref "R123")
      (value "10k")
      (footprint "0805R")
      (description "Resistor")
      (fields
        (field (name "MANUFACTURER") "Generic Components")
        (field (name "PUBLISHER") "Altium Hobart Technology Centre")
      )
      (libsource (lib "Miscellaneous Devices") (part "Res1"))
    )
    (comp (ref "R124")
      (value "3.3k")
      (footprint "0805R")
      (description "Resistor")
      (fields
        (field (name "MANUFACTURER") "Generic Components")
        (field (name "PUBLISHER") "Altium Hobart Technology Centre")
      )
      (libsource (lib "Miscellaneous Devices") (part "Res1"))
    )
    (comp (ref "SMA_ANT")
      (value "SMA_ANT")
      (footprint "SMA_ANT")
      (libsource (lib "Main_Board") (part "SMA_ANT"))
    )
    (comp (ref "U1")
      (value "MCU_LQFP144")
      (footprint "Main_Board:LQFP144_0R5_SKT")
      (libsource (lib "Main_Board") (part "MCU_LQFP144"))
    )
    (comp (ref "U2")
      (value "PCA9539_PW_24")
      (footprint "Main_Board:PW24-L_pca9539")
      (fields
        (field (name "MANUFACTURER_PART_NUMBER") "pca9539_pw_24")
        (field (name "GENERIC_PART_NUMBER") "PCA9539")
        (field (name "MANUFACTURER") "Texas Instruments")
      )
      (libsource (lib "Main_Board") (part "PCA9539_PW_24"))
    )
    (comp (ref "U3")
      (value "TL4050A10_DBZ_3")
      (footprint "Main_Board:DBZ3-L")
      (description "Precision Micropower Shunt Voltage Reference")
      (fields
        (field (name "MANUFACTURER_PART_NUMBER") "tl4050a10_dbz_3")
        (field (name "GENERIC_PART_NUMBER") "TL4050A10")
      )
      (libsource (lib "Main_Board") (part "TL4050A10_DBZ_3"))
    )
    (comp (ref "U4")
      (value "MC34152D")
      (footprint "SO-G8")
      (description "High Speed Dual MOSFET Driver")
      (fields
        (field (name "MANUFACTURER") "Motorola")
        (field (name "PUBLISHER") "Altium Hobart Technology Centre")
      )
      (libsource (lib "Motorola Interface MOSFET Driver") (part "MC34152D"))
    )
    (comp (ref "U6")
      (value "NRF2401P+")
      (footprint "Main_Board:NRF2401P+_zeyao")
      (libsource (lib "Main_Board") (part "NRF2401P+"))
    )
    (comp (ref "U12")
      (value "CH340B")
      (footprint "Main_Board:SOP16")
      (libsource (lib "Main_Board") (part "CH340B"))
    )
    (comp (ref "U23")
      (value "miniusb")
      (footprint "miniusb 180")
      (libsource (lib "Main_Board") (part "miniusb"))
    )
    (comp (ref "U25")
      (value "LPMS-NAV2")
      (footprint "LPMS-NAV2")
      (libsource (lib "Main_Board") (part "LPMS-NAV2"))
    )
    (comp (ref "U26")
      (value "ADS112C04IPWR")
      (footprint "TSSOP_PW0016A_ADS112C04")
      (description "Imported")
      (fields (field (name "MANUFACTURER") "Texas Instruments"))
      (libsource (lib "Main_Board") (part "ADS112C04IPWR"))
    )
    (comp (ref "X1")
      (value "32.768KHZ")
      (footprint "Main_Board:FC-255")
      (description "Crystal")
      (libsource (lib "Main_Board") (part "CRYSTAL"))
    )
    (comp (ref "X2")
      (value "8MHZ")
      (footprint "Main_Board:5032")
      (description "Crystal or Oscillator")
      (fields
        (field (name "MANUFACTURER_PART_NUMBER") "ECS-80-18-30B-AGN-TR")
        (field (name "MOUSER PART NUMBER") "520-80-18-30B-AGNT")
      )
      (libsource (lib "SamacSys") (part "ECS-80-18-30B-AGN-TR"))
    )
  )
  (nets
    (net (code "1") (name "+3.3V") (class "Default")
      (node (ref "C10") (pin "2") (pinfunction "2_2") (pintype "passive"))
      (node (ref "C103") (pin "1") (pinfunction "+_1") (pintype "passive"))
      (node (ref "C104") (pin "1") (pinfunction "1_1") (pintype "passive"))
      (node (ref "C41") (pin "1") (pinfunction "1_1") (pintype "passive"))
      (node (ref "C42") (pin "1") (pinfunction "1_1") (pintype "passive"))
      (node (ref "C43") (pin "1") (pinfunction "1_1") (pintype "passive"))
      (node (ref "C44") (pin "1") (pinfunction "1_1") (pintype "passive"))
      (node (ref "C45") (pin "1") (pinfunction "1_1") (pintype "passive"))
      (node (ref "C54") (pin "1") (pinfunction "1_1") (pintype "passive"))
      (node (ref "C55") (pin "1") (pinfunction "1_1") (pintype "passive"))
      (node (ref "C66") (pin "1") (pinfunction "1_1") (pintype "passive"))
      (node (ref "C67") (pin "1") (pinfunction "1_1") (pintype "passive"))
      (node (ref "C78") (pin "1") (pinfunction "1_1") (pintype "passive"))
      (node (ref "C79") (pin "1") (pinfunction "1_1") (pintype "passive"))
      (node (ref "C85") (pin "1") (pinfunction "1_1") (pintype "passive"))
      (node (ref "C9") (pin "2") (pinfunction "2_2") (pintype "passive"))
      (node (ref "C91") (pin "1") (pinfunction "1_1") (pintype "passive"))
      (node (ref "C99") (pin "2") (pinfunction "2_2") (pintype "passive"))
      (node (ref "DS1") (pin "1") (pinfunction "A_1") (pintype "passive"))
      (node (ref "DS2") (pin "1") (pinfunction "A_1") (pintype "passive"))
      (node (ref "DS3") (pin "1") (pinfunction "A_1") (pintype "passive"))
      (node (ref "DS4") (pin "1") (pinfunction "A_1") (pintype "passive"))
      (node (ref "DS5") (pin "1") (pinfunction "A_1") (pintype "passive"))
      (node (ref "J") (pin "2") (pinfunction "VCC_2") (pintype "passive"))
      (node (ref "JP5") (pin "7") (pinfunction "7_7") (pintype "passive"))
      (node (ref "JP6") (pin "1") (pinfunction "1_1") (pintype "passive"))
      (node (ref "R103") (pin "2") (pinfunction "2_2") (pintype "passive"))
      (node (ref "R104") (pin "2") (pinfunction "2_2") (pintype "passive"))
      (node (ref "R105") (pin "2") (pinfunction "2_2") (pintype "passive"))
      (node (ref "R106") (pin "2") (pinfunction "2_2") (pintype "passive"))
      (node (ref "R11") (pin "2") (pinfunction "2_2") (pintype "passive"))
      (node (ref "R119") (pin "2") (pinfunction "2_2") (pintype "passive"))
      (node (ref "R12") (pin "2") (pinfunction "2_2") (pintype "passive"))
      (node (ref "R120") (pin "2") (pinfunction "2_2") (pintype "passive"))
      (node (ref "R121") (pin "2") (pinfunction "2_2") (pintype "passive"))
      (node (ref "R122") (pin "2") (pinfunction "2_2") (pintype "passive"))
      (node (ref "R123") (pin "2") (pinfunction "2_2") (pintype "passive"))
      (node (ref "R13") (pin "2") (pinfunction "2_2") (pintype "passive"))
      (node (ref "R14") (pin "2") (pinfunction "2_2") (pintype "passive"))
      (node (ref "R15") (pin "2") (pinfunction "2_2") (pintype "passive"))
      (node (ref "R16") (pin "2") (pinfunction "2_2") (pintype "passive"))
      (node (ref "R17") (pin "2") (pinfunction "2_2") (pintype "passive"))
      (node (ref "R18") (pin "2") (pinfunction "2_2") (pintype "passive"))
      (node (ref "R19") (pin "2") (pinfunction "2_2") (pintype "passive"))
      (node (ref "R20") (pin "2") (pinfunction "2_2") (pintype "passive"))
      (node (ref "R21") (pin "2") (pinfunction "2_2") (pintype "passive"))
      (node (ref "R22") (pin "2") (pinfunction "2_2") (pintype "passive"))
      (node (ref "R23") (pin "1") (pinfunction "1_1") (pintype "passive"))
      (node (ref "R24") (pin "1") (pinfunction "1_1") (pintype "passive"))
      (node (ref "R35") (pin "2") (pinfunction "2_2") (pintype "passive"))
      (node (ref "R40") (pin "2") (pinfunction "2_2") (pintype "passive"))
      (node (ref "R41") (pin "2") (pinfunction "2_2") (pintype "passive"))
      (node (ref "R42") (pin "2") (pinfunction "2_2") (pintype "passive"))
      (node (ref "R48") (pin "2") (pinfunction "2_2") (pintype "passive"))
      (node (ref "R49") (pin "2") (pinfunction "2_2") (pintype "passive"))
      (node (ref "R50") (pin "2") (pinfunction "2_2") (pintype "passive"))
      (node (ref "R51") (pin "2") (pinfunction "2_2") (pintype "passive"))
      (node (ref "R91") (pin "2") (pinfunction "2_2") (pintype "passive"))
      (node (ref "R92") (pin "1") (pinfunction "1_1") (pintype "passive"))
      (node (ref "R93") (pin "1") (pinfunction "1_1") (pintype "passive"))
      (node (ref "R98") (pin "1") (pinfunction "1_1") (pintype "passive"))
      (node (ref "U1") (pin "108") (pinfunction "VDD_2_108") (pintype "passive"))
      (node (ref "U1") (pin "121") (pinfunction "VDD_10_121") (pintype "passive"))
      (node (ref "U1") (pin "131") (pinfunction "VDD_11/VDDIO_2_131") (pintype "passive"))
      (node (ref "U1") (pin "143") (pinfunction "PDR_ON/VSS_3/NC_143") (pintype "passive"))
      (node (ref "U1") (pin "144") (pinfunction "VDD_3/VDD_SA_144") (pintype "passive"))
      (node (ref "U1") (pin "17") (pinfunction "VDD_5_17") (pintype "passive"))
      (node (ref "U1") (pin "30") (pinfunction "VDD_12/VSSA_30") (pintype "passive"))
      (node (ref "U1") (pin "32") (pinfunction "VREF+_32") (pintype "passive"))
      (node (ref "U1") (pin "33") (pinfunction "VDDA_33") (pintype "passive"))
      (node (ref "U1") (pin "39") (pinfunction "VDD_4_39") (pintype "passive"))
      (node (ref "U1") (pin "52") (pinfunction "VDD_6_52") (pintype "passive"))
      (node (ref "U1") (pin "6") (pinfunction "VBAT_6") (pintype "passive"))
      (node (ref "U1") (pin "62") (pinfunction "VDD_7_62") (pintype "passive"))
      (node (ref "U1") (pin "72") (pinfunction "VDD_1_72") (pintype "passive"))
      (node (ref "U1") (pin "84") (pinfunction "VDD_8_84") (pintype "passive"))
      (node (ref "U1") (pin "95") (pinfunction "VDD_9/VDDIO_1/VDD_USB33_95") (pintype "passive"))
      (node (ref "U12") (pin "16") (pinfunction "VCC_16") (pintype "passive"))
      (node (ref "U12") (pin "4") (pinfunction "V3_4") (pintype "passive"))
      (node (ref "U2") (pin "24") (pinfunction "VCC_24") (pintype "power_in"))
      (node (ref "U25") (pin "1") (pinfunction "VDD_1") (pintype "passive"))
      (node (ref "U25") (pin "20") (pinfunction "VDD_20") (pintype "passive"))
      (node (ref "U6") (pin "1") (pinfunction "VCC_1") (pintype "passive"))
      (node (ref "header1*6pin") (pin "1") (pinfunction "1_1") (pintype "passive"))
    )
    (net (code "2") (name "+5V") (class "Default")
      (node (ref "C110") (pin "1") (pinfunction "+_1") (pintype "passive"))
      (node (ref "C111") (pin "1") (pinfunction "1_1") (pintype "passive"))
      (node (ref "C17") (pin "2") (pinfunction "2_2") (pintype "passive"))
      (node (ref "C18") (pin "2") (pinfunction "2_2") (pintype "passive"))
      (node (ref "C2") (pin "2") (pinfunction "2_2") (pintype "passive"))
      (node (ref "C3") (pin "2") (pinfunction "2_2") (pintype "passive"))
      (node (ref "C8") (pin "1") (pinfunction "1_1") (pintype "passive"))
      (node (ref "J10") (pin "1") (pinfunction "1_1") (pintype "passive"))
      (node (ref "JP5") (pin "9") (pinfunction "9_9") (pintype "passive"))
      (node (ref "LS1") (pin "1") (pinfunction "A_1") (pintype "passive"))
      (node (ref "NICERF2401F27") (pin "1") (pinfunction "VCC_1") (pintype "passive"))
      (node (ref "R1") (pin "1") (pinfunction "1_1") (pintype "passive"))
      (node (ref "R4") (pin "2") (pinfunction "2_2") (pintype "passive"))
      (node (ref "R43") (pin "2") (pinfunction "2_2") (pintype "passive"))
      (node (ref "R5") (pin "2") (pinfunction "2_2") (pintype "passive"))
      (node (ref "U26") (pin "12") (pinfunction "AVDD_12") (pintype "passive"))
      (node (ref "U26") (pin "13") (pinfunction "DVDD_13") (pintype "passive"))
    )
    (net (code "3") (name "+12V") (class "Default")
      (node (ref "C112") (pin "1") (pinfunction "1_1") (pintype "passive"))
      (node (ref "C16") (pin "1") (pinfunction "1_1") (pintype "passive"))
      (node (ref "JP5") (pin "8") (pinfunction "8_8") (pintype "passive"))
      (node (ref "U4") (pin "6") (pinfunction "VCC_6") (pintype "power_in"))
    )
    (net (code "4") (name "+16V") (class "Default")
      (node (ref "JP5") (pin "2") (pinfunction "2_2") (pintype "passive"))
      (node (ref "JP5") (pin "4") (pinfunction "4_4") (pintype "passive"))
      (node (ref "JP5") (pin "6") (pinfunction "6_6") (pintype "passive"))
      (node (ref "R44") (pin "2") (pinfunction "2_2") (pintype "passive"))
    )
    (net (code "5") (name "/+2.5V") (class "Default")
      (node (ref "C14") (pin "2") (pinfunction "2_2") (pintype "passive"))
      (node (ref "C15") (pin "2") (pinfunction "2_2") (pintype "passive"))
      (node (ref "R43") (pin "1") (pinfunction "1_1") (pintype "passive"))
      (node (ref "U26") (pin "9") (pinfunction "REFP_9") (pintype "passive"))
      (node (ref "U3") (pin "1") (pinfunction "CATHODE_1") (pintype "passive"))
    )
    (net (code "6") (name "/1280_RXEN") (class "Default")
      (node (ref "NICERF2401F27") (pin "10") (pinfunction "RXEN_10") (pintype "passive"))
      (node (ref "U1") (pin "128") (pinfunction "PG13_128") (pintype "passive"))
    )
    (net (code "7") (name "/1280_TXEN") (class "Default")
      (node (ref "NICERF2401F27") (pin "9") (pinfunction "TXEN_9") (pintype "passive"))
      (node (ref "U1") (pin "129") (pinfunction "PG14_129") (pintype "passive"))
    )
    (net (code "8") (name "/ADC_BATTERY") (class "Default")
      (node (ref "C13") (pin "2") (pinfunction "2_2") (pintype "passive"))
      (node (ref "R44") (pin "1") (pinfunction "1_1") (pintype "passive"))
      (node (ref "R45") (pin "2") (pinfunction "2_2") (pintype "passive"))
      (node (ref "U1") (pin "44") (pinfunction "PC4_44") (pintype "passive"))
    )
    (net (code "9") (name "/ADC_CAP") (class "Default")
      (node (ref "JP5") (pin "11") (pinfunction "11_11") (pintype "passive"))
      (node (ref "U1") (pin "49") (pinfunction "PF11_49") (pintype "passive"))
    )
    (net (code "10") (name "/ANT") (class "Default")
      (node (ref "NICERF2401F27") (pin "12") (pinfunction "ANT_12") (pintype "passive"))
      (node (ref "SMA_ANT") (pin "1") (pinfunction "ANT_1") (pintype "passive"))
    )
    (net (code "11") (name "/ANT_GND") (class "Default")
      (node (ref "NICERF2401F27") (pin "13") (pinfunction "ANT_GND_13") (pintype "passive"))
      (node (ref "SMA_ANT") (pin "2") (pinfunction "ANT_GND_2") (pintype "passive"))
    )
    (net (code "12") (name "/BOOT_DONE") (class "Default")
      (node (ref "R102") (pin "1") (pinfunction "1_1") (pintype "passive"))
      (node (ref "U1") (pin "116") (pinfunction "PD2_116") (pintype "passive"))
    )
    (net (code "13") (name "/Buzzer") (class "Default")
      (node (ref "R6") (pin "1") (pinfunction "1_1") (pintype "passive"))
      (node (ref "U1") (pin "18") (pinfunction "PF6_18") (pintype "passive"))
    )
    (net (code "14") (name "/CSOUT_1") (class "Default")
      (node (ref "U26") (pin "7") (pinfunction "AIN2_7") (pintype "passive"))
    )
    (net (code "15") (name "/CSOUT_2") (class "Default")
      (node (ref "U26") (pin "6") (pinfunction "AIN3_6") (pintype "passive"))
    )
    (net (code "16") (name "/CSOUT_3") (class "Default")
      (node (ref "U26") (pin "11") (pinfunction "AIN0_11") (pintype "passive"))
    )
    (net (code "17") (name "/CSOUT_4") (class "Default")
      (node (ref "U26") (pin "10") (pinfunction "AIN1_10") (pintype "passive"))
    )
    (net (code "18") (name "/CURRENT_DRDY") (class "Default")
      (node (ref "R50") (pin "1") (pinfunction "1_1") (pintype "passive"))
      (node (ref "U1") (pin "132") (pinfunction "PG15_132") (pintype "passive"))
      (node (ref "U26") (pin "14") (pinfunction "DRDY_N_14") (pintype "passive"))
    )
    (net (code "19") (name "/Chip") (class "Default")
      (node (ref "R47") (pin "2") (pinfunction "2_2") (pintype "passive"))
      (node (ref "U1") (pin "75") (pinfunction "PB14_75") (pintype "passive"))
      (node (ref "U4") (pin "4") (pinfunction "INB_4") (pintype "input"))
    )
    (net (code "20") (name "/Chip_V") (class "Default")
      (node (ref "JP5") (pin "10") (pinfunction "10_10") (pintype "passive"))
      (node (ref "U4") (pin "5") (pinfunction "~{OUTB}_5") (pintype "output"))
    )
    (net (code "21") (name "/DIR_1") (class "Default")
      (node (ref "U1") (pin "87") (pinfunction "PG2_87") (pintype "passive"))
    )
    (net (code "22") (name "/DIR_2") (class "Default")
      (node (ref "U1") (pin "15") (pinfunction "PF5_15") (pintype "passive"))
    )
    (net (code "23") (name "/DIR_3") (class "Default")
      (node (ref "U1") (pin "7") (pinfunction "PC13_7") (pintype "passive"))
    )
    (net (code "24") (name "/DIR_4") (class "Default")
      (node (ref "U1") (pin "103") (pinfunction "PA11_103") (pintype "passive"))
    )
    (net (code "25") (name "/DIR_d") (class "Default")
      (node (ref "U1") (pin "58") (pinfunction "PE7_58") (pintype "passive"))
    )
    (net (code "26") (name "/Encoder_A_1") (class "Default")
      (node (ref "U1") (pin "60") (pinfunction "PE9_60") (pintype "passive"))
    )
    (net (code "27") (name "/Encoder_A_2") (class "Default")
      (node (ref "U1") (pin "34") (pinfunction "PA0_34") (pintype "passive"))
    )
    (net (code "28") (name "/Encoder_A_3") (class "Default")
      (node (ref "U1") (pin "134") (pinfunction "PB4_134") (pintype "passive"))
    )
    (net (code "29") (name "/Encoder_A_4") (class "Default")
      (node (ref "U1") (pin "81") (pinfunction "PD12_81") (pintype "passive"))
    )
    (net (code "30") (name "/Encoder_B_1") (class "Default")
      (node (ref "U1") (pin "64") (pinfunction "PE11_64") (pintype "passive"))
    )
    (net (code "31") (name "/Encoder_B_2") (class "Default")
      (node (ref "U1") (pin "35") (pinfunction "PA1_35") (pintype "passive"))
    )
    (net (code "32") (name "/Encoder_B_3") (class "Default")
      (node (ref "U1") (pin "135") (pinfunction "PB5_135") (pintype "passive"))
    )
    (net (code "33") (name "/Encoder_B_4") (class "Default")
      (node (ref "U1") (pin "82") (pinfunction "PD13_82") (pintype "passive"))
    )
    (net (code "34") (name "/HEART") (class "Default")
      (node (ref "R34") (pin "1") (pinfunction "1_1") (pintype "passive"))
      (node (ref "U1") (pin "113") (pinfunction "PC12_113") (pintype "passive"))
    )
    (net (code "35") (name "/I2C_SCL_2") (class "Default")
      (node (ref "R49") (pin "1") (pinfunction "1_1") (pintype "passive"))
      (node (ref "U1") (pin "11") (pinfunction "PF1/PH1_11") (pintype "passive"))
      (node (ref "U26") (pin "16") (pinfunction "SCL_16") (pintype "passive"))
    )
    (net (code "36") (name "/I2C_SCL_3") (class "Default")
      (node (ref "R41") (pin "1") (pinfunction "1_1") (pintype "passive"))
      (node (ref "U1") (pin "100") (pinfunction "PA8_100") (pintype "passive"))
      (node (ref "U2") (pin "22") (pinfunction "SCL_22") (pintype "passive"))
    )
    (net (code "37") (name "/I2C_SCL_4") (class "Default")
      (node (ref "J") (pin "10") (pinfunction "SCL_10") (pintype "passive"))
      (node (ref "R91") (pin "1") (pinfunction "1_1") (pintype "passive"))
      (node (ref "U1") (pin "54") (pinfunction "PF14_54") (pintype "passive"))
    )
    (net (code "38") (name "/I2C_SDA_2") (class "Default")
      (node (ref "R48") (pin "1") (pinfunction "1_1") (pintype "passive"))
      (node (ref "U1") (pin "10") (pinfunction "PF0/PH0_10") (pintype "passive"))
      (node (ref "U26") (pin "15") (pinfunction "SDA_15") (pintype "passive"))
    )
    (net (code "39") (name "/I2C_SDA_3") (class "Default")
      (node (ref "R40") (pin "1") (pinfunction "1_1") (pintype "passive"))
      (node (ref "U1") (pin "99") (pinfunction "PC9_99") (pintype "passive"))
      (node (ref "U2") (pin "23") (pinfunction "SDA_23") (pintype "passive"))
    )
    (net (code "40") (name "/I2C_SDA_4") (class "Default")
      (node (ref "J") (pin "9") (pinfunction "SDA_9") (pintype "passive"))
      (node (ref "R92") (pin "2") (pinfunction "2_2") (pintype "passive"))
      (node (ref "U1") (pin "55") (pinfunction "PF15_55") (pintype "passive"))
    )
    (net (code "41") (name "/IMU_NRST") (class "Default")
      (node (ref "R119") (pin "1") (pinfunction "1_1") (pintype "passive"))
      (node (ref "U1") (pin "110") (pinfunction "PA15_110") (pintype "passive"))
      (node (ref "U25") (pin "2") (pinfunction "NRST_2") (pintype "passive"))
    )
    (net (code "42") (name "/IR+") (class "Default")
      (node (ref "JP2") (pin "1") (pinfunction "2_1") (pintype "passive"))
      (node (ref "R5") (pin "1") (pinfunction "1_1") (pintype "passive"))
    )
    (net (code "43") (name "/IR-") (class "Default")
      (node (ref "JP2") (pin "2") (pinfunction "1_2") (pintype "passive"))
      (node (ref "Q1") (pin "3") (pinfunction "C_3") (pintype "passive"))
    )
    (net (code "44") (name "/Infra") (class "Default")
      (node (ref "R2") (pin "1") (pinfunction "1_1") (pintype "passive"))
      (node (ref "U1") (pin "36") (pinfunction "PA2_36") (pintype "passive"))
    )
    (net (code "45") (name "/Infra_IN") (class "Default")
      (node (ref "JP1") (pin "3") (pinfunction "3_3") (pintype "passive"))
      (node (ref "R1") (pin "2") (pinfunction "2_2") (pintype "passive"))
    )
    (net (code "46") (name "/Infra_IN_V") (class "Default")
      (node (ref "U1") (pin "37") (pinfunction "PA3_37") (pintype "passive"))
    )
    (net (code "47") (name "/Infra_LED") (class "Default")
      (node (ref "R90") (pin "1") (pinfunction "1_1") (pintype "passive"))
      (node (ref "U1") (pin "45") (pinfunction "PC5_45") (pintype "passive"))
    )
    (net (code "48") (name "/Motor_DIRO_d") (class "Default")
      (node (ref "U1") (pin "42") (pinfunction "PA6_42") (pintype "passive"))
    )
    (net (code "49") (name "/Motor_FF1_1_V") (class "Default")
      (node (ref "U1") (pin "79") (pinfunction "PD10_79") (pintype "passive"))
    )
    (net (code "50") (name "/Motor_FF1_2_V") (class "Default")
      (node (ref "U1") (pin "19") (pinfunction "PF7_19") (pintype "passive"))
    )
    (net (code "51") (name "/Motor_FF1_3_V") (class "Default")
      (node (ref "U1") (pin "136") (pinfunction "PB6_136") (pintype "passive"))
    )
    (net (code "52") (name "/Motor_FF1_4_V") (class "Default")
      (node (ref "U1") (pin "92") (pinfunction "PG7_92") (pintype "passive"))
    )
    (net (code "53") (name "/Motor_FF1_d_V") (class "Default")
      (node (ref "U1") (pin "65") (pinfunction "PE12_65") (pintype "passive"))
    )
    (net (code "54") (name "/Motor_FF2_1_V") (class "Default")
      (node (ref "U1") (pin "80") (pinfunction "PD11_80") (pintype "passive"))
    )
    (net (code "55") (name "/Motor_FF2_2_V") (class "Default")
      (node (ref "U1") (pin "20") (pinfunction "PF8_20") (pintype "passive"))
    )
    (net (code "56") (name "/Motor_FF2_3_V") (class "Default")
      (node (ref "U1") (pin "137") (pinfunction "PB7_137") (pintype "passive"))
    )
    (net (code "57") (name "/Motor_FF2_4_V") (class "Default")
      (node (ref "U1") (pin "93") (pinfunction "PG8_93") (pintype "passive"))
    )
    (net (code "58") (name "/Motor_FF2_d_V") (class "Default")
      (node (ref "U1") (pin "66") (pinfunction "PE13_66") (pintype "passive"))
    )
    (net (code "59") (name "/Motor_MODE_1") (class "Default")
      (node (ref "U1") (pin "89") (pinfunction "PG4_89") (pintype "passive"))
    )
    (net (code "60") (name "/Motor_MODE_2") (class "Default")
      (node (ref "U1") (pin "21") (pinfunction "PF9_21") (pintype "passive"))
    )
    (net (code "61") (name "/Motor_MODE_3") (class "Default")
      (node (ref "U1") (pin "133") (pinfunction "PB3_133") (pintype "passive"))
    )
    (net (code "62") (name "/Motor_MODE_4") (class "Default")
      (node (ref "U1") (pin "90") (pinfunction "PG5_90") (pintype "passive"))
    )
    (net (code "63") (name "/Motor_MODE_d") (class "Default")
      (node (ref "U1") (pin "59") (pinfunction "PE8_59") (pintype "passive"))
    )
    (net (code "64") (name "/Motor_Reset_1") (class "Default")
      (node (ref "U1") (pin "88") (pinfunction "PG3_88") (pintype "passive"))
    )
    (net (code "65") (name "/Motor_Reset_2") (class "Default")
      (node (ref "U1") (pin "22") (pinfunction "PF10_22") (pintype "passive"))
    )
    (net (code "66") (name "/Motor_Reset_3") (class "Default")
      (node (ref "U1") (pin "139") (pinfunction "PB8_139") (pintype "passive"))
    )
    (net (code "67") (name "/Motor_Reset_4") (class "Default")
      (node (ref "U1") (pin "91") (pinfunction "PG6_91") (pintype "passive"))
    )
    (net (code "68") (name "/Motor_Reset_d") (class "Default")
      (node (ref "U1") (pin "63") (pinfunction "PE10_63") (pintype "passive"))
    )
    (net (code "69") (name "/Motor_TACHO_d") (class "Default")
      (node (ref "U1") (pin "5") (pinfunction "PE6_5") (pintype "passive"))
    )
    (net (code "70") (name "/NRST") (class "Default")
      (node (ref "R35") (pin "1") (pinfunction "1_1") (pintype "passive"))
      (node (ref "U1") (pin "25") (pinfunction "NRST_25") (pintype "passive"))
      (node (ref "header1*6pin") (pin "2") (pinfunction "2_2") (pintype "passive"))
    )
    (net (code "71") (name "/PCA9539_~{INT}") (class "Default")
      (node (ref "U1") (pin "119") (pinfunction "PD5_119") (pintype "passive"))
      (node (ref "U2") (pin "1") (pinfunction "~{INT}_1") (pintype "output"))
    )
    (net (code "72") (name "/PWM_1") (class "Default")
      (node (ref "U1") (pin "96") (pinfunction "PC6_96") (pintype "passive"))
    )
    (net (code "73") (name "/PWM_2") (class "Default")
      (node (ref "U1") (pin "102") (pinfunction "PA10_102") (pintype "passive"))
    )
    (net (code "74") (name "/PWM_3") (class "Default")
      (node (ref "U1") (pin "104") (pinfunction "PA12_104") (pintype "passive"))
    )
    (net (code "75") (name "/PWM_4") (class "Default")
      (node (ref "U1") (pin "98") (pinfunction "PC8_98") (pintype "passive"))
    )
    (net (code "76") (name "/PWM_d") (class "Default")
      (node (ref "U1") (pin "43") (pinfunction "PA7_43") (pintype "passive"))
    )
    (net (code "77") (name "/RX_COM") (class "Default")
      (node (ref "R124") (pin "1") (pinfunction "1_1") (pintype "passive"))
      (node (ref "U1") (pin "115") (pinfunction "PD1_115") (pintype "passive"))
    )
    (net (code "78") (name "/S1") (class "Default")
      (node (ref "P1") (pin "2") (pinfunction "GND_2") (pintype "power_in"))
      (node (ref "R14") (pin "1") (pinfunction "1_1") (pintype "passive"))
      (node (ref "R25") (pin "1") (pinfunction "1_1") (pintype "passive"))
    )
    (net (code "79") (name "/S2") (class "Default")
      (node (ref "P1") (pin "3") (pinfunction "GND_3") (pintype "power_in"))
      (node (ref "R13") (pin "1") (pinfunction "1_1") (pintype "passive"))
      (node (ref "R26") (pin "1") (pinfunction "1_1") (pintype "passive"))
    )
    (net (code "80") (name "/S3") (class "Default")
      (node (ref "P1") (pin "4") (pinfunction "GND_4") (pintype "power_in"))
      (node (ref "R12") (pin "1") (pinfunction "1_1") (pintype "passive"))
      (node (ref "R27") (pin "1") (pinfunction "1_1") (pintype "passive"))
    )
    (net (code "81") (name "/S4") (class "Default")
      (node (ref "P1") (pin "5") (pinfunction "GND_5") (pintype "power_in"))
      (node (ref "R11") (pin "1") (pinfunction "1_1") (pintype "passive"))
      (node (ref "R28") (pin "1") (pinfunction "1_1") (pintype "passive"))
    )
    (net (code "82") (name "/S5") (class "Default")
      (node (ref "P2") (pin "2") (pinfunction "GND_2") (pintype "power_in"))
      (node (ref "R18") (pin "1") (pinfunction "1_1") (pintype "passive"))
      (node (ref "R29") (pin "1") (pinfunction "1_1") (pintype "passive"))
    )
    (net (code "83") (name "/S6") (class "Default")
      (node (ref "P2") (pin "3") (pinfunction "GND_3") (pintype "power_in"))
      (node (ref "R17") (pin "1") (pinfunction "1_1") (pintype "passive"))
      (node (ref "R30") (pin "1") (pinfunction "1_1") (pintype "passive"))
    )
    (net (code "84") (name "/S7") (class "Default")
      (node (ref "P2") (pin "4") (pinfunction "GND_4") (pintype "power_in"))
      (node (ref "R16") (pin "1") (pinfunction "1_1") (pintype "passive"))
      (node (ref "R31") (pin "1") (pinfunction "1_1") (pintype "passive"))
    )
    (net (code "85") (name "/S8") (class "Default")
      (node (ref "P2") (pin "5") (pinfunction "GND_5") (pintype "power_in"))
      (node (ref "R15") (pin "1") (pinfunction "1_1") (pintype "passive"))
      (node (ref "R32") (pin "1") (pinfunction "1_1") (pintype "passive"))
    )
    (net (code "86") (name "/S9") (class "Default")
      (node (ref "P3") (pin "2") (pinfunction "GND_2") (pintype "power_in"))
      (node (ref "R22") (pin "1") (pinfunction "1_1") (pintype "passive"))
      (node (ref "R39") (pin "2") (pinfunction "2_2") (pintype "passive"))
    )
    (net (code "87") (name "/S10") (class "Default")
      (node (ref "P3") (pin "3") (pinfunction "GND_3") (pintype "power_in"))
      (node (ref "R21") (pin "1") (pinfunction "1_1") (pintype "passive"))
      (node (ref "R38") (pin "2") (pinfunction "2_2") (pintype "passive"))
    )
    (net (code "88") (name "/S11") (class "Default")
      (node (ref "P3") (pin "4") (pinfunction "GND_4") (pintype "power_in"))
      (node (ref "R20") (pin "1") (pinfunction "1_1") (pintype "passive"))
      (node (ref "R37") (pin "2") (pinfunction "2_2") (pintype "passive"))
    )
    (net (code "89") (name "/S12") (class "Default")
      (node (ref "P3") (pin "5") (pinfunction "GND_5") (pintype "power_in"))
      (node (ref "R19") (pin "1") (pinfunction "1_1") (pintype "passive"))
      (node (ref "R36") (pin "2") (pinfunction "2_2") (pintype "passive"))
    )
    (net (code "90") (name "/S13") (class "Default")
      (node (ref "P25") (pin "2") (pinfunction "GND_2") (pintype "power_in"))
      (node (ref "R106") (pin "1") (pinfunction "1_1") (pintype "passive"))
      (node (ref "R107") (pin "2") (pinfunction "2_2") (pintype "passive"))
    )
    (net (code "91") (name "/S14") (class "Default")
      (node (ref "P25") (pin "3") (pinfunction "GND_3") (pintype "power_in"))
      (node (ref "R105") (pin "1") (pinfunction "1_1") (pintype "passive"))
      (node (ref "R108") (pin "2") (pinfunction "2_2") (pintype "passive"))
    )
    (net (code "92") (name "/S15") (class "Default")
      (node (ref "P25") (pin "4") (pinfunction "GND_4") (pintype "power_in"))
      (node (ref "R104") (pin "1") (pinfunction "1_1") (pintype "passive"))
      (node (ref "R109") (pin "2") (pinfunction "2_2") (pintype "passive"))
    )
    (net (code "93") (name "/S16") (class "Default")
      (node (ref "P25") (pin "5") (pinfunction "GND_5") (pintype "power_in"))
      (node (ref "R103") (pin "1") (pinfunction "1_1") (pintype "passive"))
      (node (ref "R110") (pin "2") (pinfunction "2_2") (pintype "passive"))
    )
    (net (code "94") (name "/SPI_CE_1") (class "Default")
      (node (ref "U1") (pin "122") (pinfunction "PD6_122") (pintype "passive"))
      (node (ref "U6") (pin "2") (pinfunction "CE_2") (pintype "passive"))
    )
    (net (code "95") (name "/SPI_CE_2") (class "Default")
      (node (ref "NICERF2401F27") (pin "3") (pinfunction "CE_3") (pintype "passive"))
      (node (ref "U1") (pin "68") (pinfunction "PE15_68") (pintype "passive"))
    )
    (net (code "96") (name "/SPI_CE_3") (class "Default")
      (node (ref "J") (pin "3") (pinfunction "CE_3") (pintype "passive"))
      (node (ref "U1") (pin "117") (pinfunction "PD3_117") (pintype "passive"))
    )
    (net (code "97") (name "/SPI_IRQ_1") (class "Default")
      (node (ref "U1") (pin "127") (pinfunction "PG12_127") (pintype "passive"))
      (node (ref "U6") (pin "7") (pinfunction "IRQ_7") (pintype "passive"))
    )
    (net (code "98") (name "/SPI_IRQ_2") (class "Default")
      (node (ref "NICERF2401F27") (pin "8") (pinfunction "IRQ_8") (pintype "passive"))
      (node (ref "U1") (pin "74") (pinfunction "PB13_74") (pintype "passive"))
    )
    (net (code "99") (name "/SPI_IRQ_3") (class "Default")
      (node (ref "J") (pin "8") (pinfunction "IRQ_8") (pintype "passive"))
      (node (ref "U1") (pin "50") (pinfunction "PF12_50") (pintype "passive"))
    )
    (net (code "100") (name "/SPI_MISO_1") (class "Default")
      (node (ref "U1") (pin "124") (pinfunction "PG9_124") (pintype "passive"))
      (node (ref "U6") (pin "6") (pinfunction "MISO_6") (pintype "passive"))
    )
    (net (code "101") (name "/SPI_MISO_2") (class "Default")
      (node (ref "NICERF2401F27") (pin "7") (pinfunction "MISO_7") (pintype "passive"))
      (node (ref "U1") (pin "28") (pinfunction "PC2_28") (pintype "passive"))
    )
    (net (code "102") (name "/SPI_MISO_3") (class "Default")
      (node (ref "J") (pin "7") (pinfunction "MISO_7") (pintype "passive"))
      (node (ref "U1") (pin "112") (pinfunction "PC11_112") (pintype "passive"))
    )
    (net (code "103") (name "/SPI_MOSI_1") (class "Default")
      (node (ref "U1") (pin "123") (pinfunction "PD7_123") (pintype "passive"))
      (node (ref "U6") (pin "5") (pinfunction "MOSI_5") (pintype "passive"))
    )
    (net (code "104") (name "/SPI_MOSI_2") (class "Default")
      (node (ref "NICERF2401F27") (pin "6") (pinfunction "MOSI_6") (pintype "passive"))
      (node (ref "U1") (pin "27") (pinfunction "PC1_27") (pintype "passive"))
    )
    (net (code "105") (name "/SPI_MOSI_3") (class "Default")
      (node (ref "J") (pin "6") (pinfunction "MOSI_6") (pintype "passive"))
      (node (ref "U1") (pin "48") (pinfunction "PB2_48") (pintype "passive"))
    )
    (net (code "106") (name "/SPI_NSS_1") (class "Default")
      (node (ref "U1") (pin "125") (pinfunction "PG10_125") (pintype "passive"))
      (node (ref "U6") (pin "3") (pinfunction "CSN_3") (pintype "passive"))
    )
    (net (code "107") (name "/SPI_NSS_2") (class "Default")
      (node (ref "NICERF2401F27") (pin "4") (pinfunction "CSN_4") (pintype "passive"))
      (node (ref "U1") (pin "73") (pinfunction "PB12_73") (pintype "passive"))
    )
    (net (code "108") (name "/SPI_NSS_3") (class "Default")
      (node (ref "J") (pin "4") (pinfunction "CSN_4") (pintype "passive"))
      (node (ref "U1") (pin "40") (pinfunction "PA4_40") (pintype "passive"))
    )
    (net (code "109") (name "/SPI_SCK_1") (class "Default")
      (node (ref "U1") (pin "126") (pinfunction "PG11_126") (pintype "passive"))
      (node (ref "U6") (pin "4") (pinfunction "SCK_4") (pintype "passive"))
    )
    (net (code "110") (name "/SPI_SCK_2") (class "Default")
      (node (ref "NICERF2401F27") (pin "5") (pinfunction "SCK_5") (pintype "passive"))
      (node (ref "U1") (pin "69") (pinfunction "PB10_69") (pintype "passive"))
    )
    (net (code "111") (name "/SPI_SCK_3") (class "Default")
      (node (ref "J") (pin "5") (pinfunction "SCK_5") (pintype "passive"))
      (node (ref "U1") (pin "111") (pinfunction "PC10_111") (pintype "passive"))
    )
    (net (code "112") (name "/SWD_SWCLK") (class "Default")
      (node (ref "R94") (pin "2") (pinfunction "2_2") (pintype "passive"))
      (node (ref "U1") (pin "109") (pinfunction "PA14_109") (pintype "passive"))
      (node (ref "header1*6pin") (pin "4") (pinfunction "4_4") (pintype "passive"))
    )
    (net (code "113") (name "/SWD_SWDIO") (class "Default")
      (node (ref "R93") (pin "2") (pinfunction "2_2") (pintype "passive"))
      (node (ref "U1") (pin "105") (pinfunction "PA13_105") (pintype "passive"))
      (node (ref "header1*6pin") (pin "5") (pinfunction "5_5") (pintype "passive"))
    )
    (net (code "114") (name "/Shoot") (class "Default")
      (node (ref "R46") (pin "2") (pinfunction "2_2") (pintype "passive"))
      (node (ref "U1") (pin "76") (pinfunction "PB15_76") (pintype "passive"))
      (node (ref "U4") (pin "2") (pinfunction "INA_2") (pintype "input"))
    )
    (net (code "115") (name "/Shoot_V") (class "Default")
      (node (ref "JP5") (pin "12") (pinfunction "12_12") (pintype "passive"))
      (node (ref "U4") (pin "7") (pinfunction "~{OUTA}_7") (pintype "output"))
    )
    (net (code "116") (name "/TX_COM") (class "Default")
      (node (ref "R33") (pin "1") (pinfunction "1_1") (pintype "passive"))
      (node (ref "U1") (pin "114") (pinfunction "PD0_114") (pintype "passive"))
    )
    (net (code "117") (name "/UART8_CTS") (class "Default")
      (node (ref "JP6") (pin "2") (pinfunction "2_2") (pintype "passive"))
      (node (ref "R120") (pin "1") (pinfunction "1_1") (pintype "passive"))
      (node (ref "U1") (pin "85") (pinfunction "PD14_85") (pintype "passive"))
      (node (ref "U25") (pin "11") (pinfunction "RTS_11") (pintype "passive"))
    )
    (net (code "118") (name "/UART8_RTS") (class "Default")
      (node (ref "JP6") (pin "4") (pinfunction "4_4") (pintype "passive"))
      (node (ref "R121") (pin "1") (pinfunction "1_1") (pintype "passive"))
      (node (ref "U1") (pin "86") (pinfunction "PD15_86") (pintype "passive"))
      (node (ref "U25") (pin "12") (pinfunction "CTS_12") (pintype "passive"))
    )
    (net (code "119") (name "/UART8_RX") (class "Default")
      (node (ref "JP6") (pin "5") (pinfunction "5_5") (pintype "passive"))
      (node (ref "R123") (pin "1") (pinfunction "1_1") (pintype "passive"))
      (node (ref "U1") (pin "141") (pinfunction "PE0_141") (pintype "passive"))
      (node (ref "U25") (pin "14") (pinfunction "TX_14") (pintype "passive"))
    )
    (net (code "120") (name "/UART8_TX") (class "Default")
      (node (ref "JP6") (pin "3") (pinfunction "3_3") (pintype "passive"))
      (node (ref "R122") (pin "1") (pinfunction "1_1") (pintype "passive"))
      (node (ref "U1") (pin "142") (pinfunction "PE1_142") (pintype "passive"))
      (node (ref "U25") (pin "13") (pinfunction "RX_13") (pintype "passive"))
    )
    (net (code "121") (name "/UD+") (class "Default")
      (node (ref "U12") (pin "5") (pinfunction "UD+_5") (pintype "passive"))
      (node (ref "U23") (pin "3") (pinfunction "D+_3") (pintype "passive"))
    )
    (net (code "122") (name "/UD-") (class "Default")
      (node (ref "U12") (pin "6") (pinfunction "UD-_6") (pintype "passive"))
      (node (ref "U23") (pin "2") (pinfunction "D-_2") (pintype "passive"))
    )
    (net (code "123") (name "/USART3_RX") (class "Default")
      (node (ref "U1") (pin "78") (pinfunction "PD9_78") (pintype "passive"))
      (node (ref "U12") (pin "2") (pinfunction "TXD_2") (pintype "passive"))
    )
    (net (code "124") (name "/USART3_TX") (class "Default")
      (node (ref "U1") (pin "77") (pinfunction "PD8_77") (pintype "passive"))
      (node (ref "U12") (pin "3") (pinfunction "RXD_3") (pintype "passive"))
    )
    (net (code "125") (name "GND") (class "Default")
      (node (ref "C1") (pin "2") (pinfunction "2_2") (pintype "passive"))
      (node (ref "C10") (pin "1") (pinfunction "1_1") (pintype "passive"))
      (node (ref "C103") (pin "2") (pinfunction "-_2") (pintype "passive"))
      (node (ref "C104") (pin "2") (pinfunction "2_2") (pintype "passive"))
      (node (ref "C11") (pin "1") (pinfunction "1_1") (pintype "passive"))
      (node (ref "C110") (pin "2") (pinfunction "-_2") (pintype "passive"))
      (node (ref "C111") (pin "2") (pinfunction "2_2") (pintype "passive"))
      (node (ref "C112") (pin "2") (pinfunction "2_2") (pintype "passive"))
      (node (ref "C12") (pin "1") (pinfunction "1_1") (pintype "passive"))
      (node (ref "C13") (pin "1") (pinfunction "1_1") (pintype "passive"))
      (node (ref "C14") (pin "1") (pinfunction "1_1") (pintype "passive"))
      (node (ref "C15") (pin "1") (pinfunction "1_1") (pintype "passive"))
      (node (ref "C16") (pin "2") (pinfunction "2_2") (pintype "passive"))
      (node (ref "C17") (pin "1") (pinfunction "1_1") (pintype "passive"))
      (node (ref "C18") (pin "1") (pinfunction "1_1") (pintype "passive"))
      (node (ref "C2") (pin "1") (pinfunction "1_1") (pintype "passive"))
      (node (ref "C3") (pin "1") (pinfunction "1_1") (pintype "passive"))
      (node (ref "C41") (pin "2") (pinfunction "2_2") (pintype "passive"))
      (node (ref "C42") (pin "2") (pinfunction "2_2") (pintype "passive"))
      (node (ref "C43") (pin "2") (pinfunction "2_2") (pintype "passive"))
      (node (ref "C44") (pin "2") (pinfunction "2_2") (pintype "passive"))
      (node (ref "C45") (pin "2") (pinfunction "2_2") (pintype "passive"))
      (node (ref "C54") (pin "2") (pinfunction "2_2") (pintype "passive"))
      (node (ref "C55") (pin "2") (pinfunction "2_2") (pintype "passive"))
      (node (ref "C66") (pin "2") (pinfunction "2_2") (pintype "passive"))
      (node (ref "C67") (pin "2") (pinfunction "2_2") (pintype "passive"))
      (node (ref "C78") (pin "2") (pinfunction "2_2") (pintype "passive"))
      (node (ref "C79") (pin "2") (pinfunction "2_2") (pintype "passive"))
      (node (ref "C8") (pin "2") (pinfunction "2_2") (pintype "passive"))
      (node (ref "C85") (pin "2") (pinfunction "2_2") (pintype "passive"))
      (node (ref "C9") (pin "1") (pinfunction "1_1") (pintype "passive"))
      (node (ref "C91") (pin "2") (pinfunction "2_2") (pintype "passive"))
      (node (ref "C95") (pin "2") (pinfunction "2_2") (pintype "passive"))
      (node (ref "C96") (pin "2") (pinfunction "2_2") (pintype "passive"))
      (node (ref "C97") (pin "2") (pinfunction "2_2") (pintype "passive"))
      (node (ref "C98") (pin "2") (pinfunction "2_2") (pintype "passive"))
      (node (ref "C99") (pin "1") (pinfunction "1_1") (pintype "passive"))
      (node (ref "J") (pin "1") (pinfunction "GND_1") (pintype "passive"))
      (node (ref "J10") (pin "2") (pinfunction "2_2") (pintype "passive"))
      (node (ref "JP1") (pin "2") (pinfunction "2_2") (pintype "passive"))
      (node (ref "JP5") (pin "1") (pinfunction "1_1") (pintype "passive"))
      (node (ref "JP5") (pin "3") (pinfunction "3_3") (pintype "passive"))
      (node (ref "JP5") (pin "5") (pinfunction "5_5") (pintype "passive"))
      (node (ref "JP6") (pin "6") (pinfunction "6_6") (pintype "passive"))
      (node (ref "NICERF2401F27") (pin "11") (pinfunction "GND_11") (pintype "passive"))
      (node (ref "NICERF2401F27") (pin "14") (pinfunction "GND_14") (pintype "passive"))
      (node (ref "NICERF2401F27") (pin "2") (pinfunction "GND_2") (pintype "passive"))
      (node (ref "P1") (pin "1") (pinfunction "Signal_1") (pintype "input"))
      (node (ref "P2") (pin "1") (pinfunction "Signal_1") (pintype "input"))
      (node (ref "P25") (pin "1") (pinfunction "Signal_1") (pintype "input"))
      (node (ref "P3") (pin "1") (pinfunction "Signal_1") (pintype "input"))
      (node (ref "P4") (pin "1") (pinfunction "1_1") (pintype "passive"))
      (node (ref "P5") (pin "1") (pinfunction "1_1") (pintype "passive"))
      (node (ref "P6") (pin "1") (pinfunction "1_1") (pintype "passive"))
      (node (ref "P7") (pin "1") (pinfunction "1_1") (pintype "passive"))
      (node (ref "Q1") (pin "2") (pinfunction "E_2") (pintype "passive"))
      (node (ref "Q2") (pin "2") (pinfunction "E_2") (pintype "passive"))
      (node (ref "R101") (pin "2") (pinfunction "2_2") (pintype "passive"))
      (node (ref "R3") (pin "2") (pinfunction "2_2") (pintype "passive"))
      (node (ref "R45") (pin "1") (pinfunction "1_1") (pintype "passive"))
      (node (ref "R46") (pin "1") (pinfunction "1_1") (pintype "passive"))
      (node (ref "R47") (pin "1") (pinfunction "1_1") (pintype "passive"))
      (node (ref "R7") (pin "2") (pinfunction "2_2") (pintype "passive"))
      (node (ref "R94") (pin "1") (pinfunction "1_1") (pintype "passive"))
      (node (ref "U1") (pin "107") (pinfunction "VSS_2_107") (pintype "passive"))
      (node (ref "U1") (pin "120") (pinfunction "VSS_10_120") (pintype "passive"))
      (node (ref "U1") (pin "130") (pinfunction "VSS_11/VSSIO_2_130") (pintype "passive"))
      (node (ref "U1") (pin "16") (pinfunction "VSS_5_16") (pintype "passive"))
      (node (ref "U1") (pin "31") (pinfunction "VSSA/VREF-_31") (pintype "passive"))
      (node (ref "U1") (pin "38") (pinfunction "VSS_4/BYPASS_REG_38") (pintype "passive"))
      (node (ref "U1") (pin "51") (pinfunction "VSS_6_51") (pintype "passive"))
      (node (ref "U1") (pin "61") (pinfunction "VSS_7_61") (pintype "passive"))
      (node (ref "U1") (pin "83") (pinfunction "VSS_8_83") (pintype "passive"))
      (node (ref "U1") (pin "94") (pinfunction "VSS_9/VSSIO_1_94") (pintype "passive"))
      (node (ref "U12") (pin "1") (pinfunction "GND_1") (pintype "passive"))
      (node (ref "U2") (pin "12") (pinfunction "GND_12") (pintype "power_in"))
      (node (ref "U23") (pin "5") (pinfunction "GND_5") (pintype "passive"))
      (node (ref "U25") (pin "10") (pinfunction "GND_10") (pintype "passive"))
      (node (ref "U25") (pin "15") (pinfunction "GND_15") (pintype "passive"))
      (node (ref "U25") (pin "17") (pinfunction "GND_17") (pintype "passive"))
      (node (ref "U25") (pin "5") (pinfunction "GND_5") (pintype "passive"))
      (node (ref "U26") (pin "1") (pinfunction "A0_1") (pintype "passive"))
      (node (ref "U26") (pin "2") (pinfunction "A1_2") (pintype "passive"))
      (node (ref "U26") (pin "4") (pinfunction "DGND_4") (pintype "passive"))
      (node (ref "U26") (pin "5") (pinfunction "AVSS_5") (pintype "passive"))
      (node (ref "U26") (pin "8") (pinfunction "REFN_8") (pintype "passive"))
      (node (ref "U3") (pin "2") (pinfunction "ANODE_2") (pintype "passive"))
      (node (ref "U3") (pin "3") (pinfunction "ANODE_3") (pintype "passive"))
      (node (ref "U4") (pin "3") (pinfunction "GND_3") (pintype "power_in"))
      (node (ref "U6") (pin "8") (pinfunction "GND_8") (pintype "passive"))
      (node (ref "X2") (pin "2") (pinfunction "GND_1_2") (pintype "passive"))
      (node (ref "X2") (pin "4") (pinfunction "GND_2_4") (pintype "passive"))
      (node (ref "header1*6pin") (pin "6") (pinfunction "6_6") (pintype "passive"))
    )
    (net (code "126") (name "Net-(C1-Pad1)") (class "Default")
      (node (ref "C1") (pin "1") (pinfunction "1_1") (pintype "passive"))
      (node (ref "JP1") (pin "1") (pinfunction "1_1") (pintype "passive"))
      (node (ref "R4") (pin "1") (pinfunction "1_1") (pintype "passive"))
    )
    (net (code "127") (name "Net-(DS1-K)") (class "Default")
      (node (ref "DS1") (pin "2") (pinfunction "K_2") (pintype "passive"))
      (node (ref "R90") (pin "2") (pinfunction "2_2") (pintype "passive"))
    )
    (net (code "128") (name "Net-(DS2-K)") (class "Default")
      (node (ref "DS2") (pin "2") (pinfunction "K_2") (pintype "passive"))
      (node (ref "R33") (pin "2") (pinfunction "2_2") (pintype "passive"))
    )
    (net (code "129") (name "Net-(DS3-K)") (class "Default")
      (node (ref "DS3") (pin "2") (pinfunction "K_2") (pintype "passive"))
      (node (ref "R34") (pin "2") (pinfunction "2_2") (pintype "passive"))
    )
    (net (code "130") (name "Net-(DS4-K)") (class "Default")
      (node (ref "DS4") (pin "2") (pinfunction "K_2") (pintype "passive"))
      (node (ref "R102") (pin "2") (pinfunction "2_2") (pintype "passive"))
    )
    (net (code "131") (name "Net-(DS5-K)") (class "Default")
      (node (ref "DS5") (pin "2") (pinfunction "K_2") (pintype "passive"))
      (node (ref "R124") (pin "2") (pinfunction "2_2") (pintype "passive"))
    )
    (net (code "132") (name "Net-(LS1-B)") (class "Default")
      (node (ref "LS1") (pin "2") (pinfunction "B_2") (pintype "passive"))
      (node (ref "Q2") (pin "3") (pinfunction "C_3") (pintype "passive"))
    )
    (net (code "133") (name "Net-(Q1-B)") (class "Default")
      (node (ref "Q1") (pin "1") (pinfunction "B_1") (pintype "passive"))
      (node (ref "R2") (pin "2") (pinfunction "2_2") (pintype "passive"))
      (node (ref "R3") (pin "1") (pinfunction "1_1") (pintype "passive"))
    )
    (net (code "134") (name "Net-(Q2-B)") (class "Default")
      (node (ref "Q2") (pin "1") (pinfunction "B_1") (pintype "passive"))
      (node (ref "R6") (pin "2") (pinfunction "2_2") (pintype "passive"))
      (node (ref "R7") (pin "1") (pinfunction "1_1") (pintype "passive"))
    )
    (net (code "135") (name "Net-(U1A-PC14-OSC32_IN)") (class "Default")
      (node (ref "C95") (pin "1") (pinfunction "1_1") (pintype "passive"))
      (node (ref "U1") (pin "8") (pinfunction "PC14-OSC32_IN_8") (pintype "passive"))
      (node (ref "X1") (pin "2") (pinfunction "2_2") (pintype "passive"))
    )
    (net (code "136") (name "Net-(U1A-PC15-OSC32_OUT)") (class "Default")
      (node (ref "C96") (pin "1") (pinfunction "1_1") (pintype "passive"))
      (node (ref "U1") (pin "9") (pinfunction "PC15-OSC32_OUT_9") (pintype "passive"))
      (node (ref "X1") (pin "1") (pinfunction "1_1") (pintype "passive"))
    )
    (net (code "137") (name "Net-(U1C-BOOT0)") (class "Default")
      (node (ref "R101") (pin "1") (pinfunction "1_1") (pintype "passive"))
      (node (ref "U1") (pin "138") (pinfunction "BOOT0_138") (pintype "passive"))
    )
    (net (code "138") (name "Net-(U1C-PH0{slash}PF0-OSC_IN)") (class "Default")
      (node (ref "C97") (pin "1") (pinfunction "1_1") (pintype "passive"))
      (node (ref "U1") (pin "23") (pinfunction "PH0/PF0-OSC_IN_23") (pintype "passive"))
      (node (ref "X2") (pin "1") (pinfunction "IN/OUT_1") (pintype "passive"))
    )
    (net (code "139") (name "Net-(U1C-PH1{slash}PF1-OSC_OUT)") (class "Default")
      (node (ref "C98") (pin "1") (pinfunction "1_1") (pintype "passive"))
      (node (ref "U1") (pin "24") (pinfunction "PH1/PF1-OSC_OUT_24") (pintype "passive"))
      (node (ref "X2") (pin "3") (pinfunction "OUT/IN_3") (pintype "passive"))
    )
    (net (code "140") (name "Net-(U1C-VCAP1{slash}VSS_1)") (class "Default")
      (node (ref "C12") (pin "2") (pinfunction "2_2") (pintype "passive"))
      (node (ref "U1") (pin "71") (pinfunction "VCAP1/VSS_1_71") (pintype "passive"))
    )
    (net (code "141") (name "Net-(U1C-VCAP2{slash}PH2{slash}VDDUSB)") (class "Default")
      (node (ref "C11") (pin "2") (pinfunction "2_2") (pintype "passive"))
      (node (ref "U1") (pin "106") (pinfunction "VCAP2/PH2/VDDUSB_106") (pintype "passive"))
    )
    (net (code "142") (name "Net-(U2-A0)") (class "Default")
      (node (ref "R42") (pin "1") (pinfunction "1_1") (pintype "passive"))
      (node (ref "U2") (pin "21") (pinfunction "A0_21") (pintype "input"))
    )
    (net (code "143") (name "Net-(U2-A1)") (class "Default")
      (node (ref "R23") (pin "2") (pinfunction "2_2") (pintype "passive"))
      (node (ref "U2") (pin "2") (pinfunction "A1_2") (pintype "input"))
    )
    (net (code "144") (name "Net-(U2-P00)") (class "Default")
      (node (ref "R25") (pin "2") (pinfunction "2_2") (pintype "passive"))
      (node (ref "U2") (pin "4") (pinfunction "P00_4") (pintype "bidirectional"))
    )
    (net (code "145") (name "Net-(U2-P01)") (class "Default")
      (node (ref "R26") (pin "2") (pinfunction "2_2") (pintype "passive"))
      (node (ref "U2") (pin "5") (pinfunction "P01_5") (pintype "bidirectional"))
    )
    (net (code "146") (name "Net-(U2-P02)") (class "Default")
      (node (ref "R27") (pin "2") (pinfunction "2_2") (pintype "passive"))
      (node (ref "U2") (pin "6") (pinfunction "P02_6") (pintype "bidirectional"))
    )
    (net (code "147") (name "Net-(U2-P03)") (class "Default")
      (node (ref "R28") (pin "2") (pinfunction "2_2") (pintype "passive"))
      (node (ref "U2") (pin "7") (pinfunction "P03_7") (pintype "bidirectional"))
    )
    (net (code "148") (name "Net-(U2-P04)") (class "Default")
      (node (ref "R29") (pin "2") (pinfunction "2_2") (pintype "passive"))
      (node (ref "U2") (pin "8") (pinfunction "P04_8") (pintype "bidirectional"))
    )
    (net (code "149") (name "Net-(U2-P05)") (class "Default")
      (node (ref "R30") (pin "2") (pinfunction "2_2") (pintype "passive"))
      (node (ref "U2") (pin "9") (pinfunction "P05_9") (pintype "bidirectional"))
    )
    (net (code "150") (name "Net-(U2-P06)") (class "Default")
      (node (ref "R31") (pin "2") (pinfunction "2_2") (pintype "passive"))
      (node (ref "U2") (pin "10") (pinfunction "P06_10") (pintype "bidirectional"))
    )
    (net (code "151") (name "Net-(U2-P07)") (class "Default")
      (node (ref "R32") (pin "2") (pinfunction "2_2") (pintype "passive"))
      (node (ref "U2") (pin "11") (pinfunction "P07_11") (pintype "bidirectional"))
    )
    (net (code "152") (name "Net-(U2-P10)") (class "Default")
      (node (ref "R39") (pin "1") (pinfunction "1_1") (pintype "passive"))
      (node (ref "U2") (pin "13") (pinfunction "P10_13") (pintype "bidirectional"))
    )
    (net (code "153") (name "Net-(U2-P11)") (class "Default")
      (node (ref "R38") (pin "1") (pinfunction "1_1") (pintype "passive"))
      (node (ref "U2") (pin "14") (pinfunction "P11_14") (pintype "bidirectional"))
    )
    (net (code "154") (name "Net-(U2-P12)") (class "Default")
      (node (ref "R37") (pin "1") (pinfunction "1_1") (pintype "passive"))
      (node (ref "U2") (pin "15") (pinfunction "P12_15") (pintype "bidirectional"))
    )
    (net (code "155") (name "Net-(U2-P13)") (class "Default")
      (node (ref "R36") (pin "1") (pinfunction "1_1") (pintype "passive"))
      (node (ref "U2") (pin "16") (pinfunction "P13_16") (pintype "bidirectional"))
    )
    (net (code "156") (name "Net-(U2-P14)") (class "Default")
      (node (ref "R107") (pin "1") (pinfunction "1_1") (pintype "passive"))
      (node (ref "U2") (pin "17") (pinfunction "P14_17") (pintype "bidirectional"))
    )
    (net (code "157") (name "Net-(U2-P15)") (class "Default")
      (node (ref "R108") (pin "1") (pinfunction "1_1") (pintype "passive"))
      (node (ref "U2") (pin "18") (pinfunction "P15_18") (pintype "bidirectional"))
    )
    (net (code "158") (name "Net-(U2-P16)") (class "Default")
      (node (ref "R109") (pin "1") (pinfunction "1_1") (pintype "passive"))
      (node (ref "U2") (pin "19") (pinfunction "P16_19") (pintype "bidirectional"))
    )
    (net (code "159") (name "Net-(U2-P17)") (class "Default")
      (node (ref "R110") (pin "1") (pinfunction "1_1") (pintype "passive"))
      (node (ref "U2") (pin "20") (pinfunction "P17_20") (pintype "bidirectional"))
    )
    (net (code "160") (name "Net-(U2-~{RESE}T)") (class "Default")
      (node (ref "R24") (pin "2") (pinfunction "2_2") (pintype "passive"))
      (node (ref "U2") (pin "3") (pinfunction "~{RESE}T_3") (pintype "input"))
    )
    (net (code "161") (name "Net-(U12-RST#)") (class "Default")
      (node (ref "R98") (pin "2") (pinfunction "2_2") (pintype "passive"))
      (node (ref "U12") (pin "7") (pinfunction "RST#_7") (pintype "passive"))
    )
    (net (code "162") (name "Net-(U26-RESET_N)") (class "Default")
      (node (ref "R51") (pin "1") (pinfunction "1_1") (pintype "passive"))
      (node (ref "U26") (pin "3") (pinfunction "RESET_N_3") (pintype "passive"))
    )
    (net (code "163") (name "unconnected-(U1A-PA5-Pad41)") (class "Default")
      (node (ref "U1") (pin "41") (pinfunction "PA5_41") (pintype "passive"))
    )
    (net (code "164") (name "unconnected-(U1A-PA9-Pad101)") (class "Default")
      (node (ref "U1") (pin "101") (pinfunction "PA9_101") (pintype "passive"))
    )
    (net (code "165") (name "unconnected-(U1A-PB0-Pad46)") (class "Default")
      (node (ref "U1") (pin "46") (pinfunction "PB0_46") (pintype "passive"))
    )
    (net (code "166") (name "unconnected-(U1A-PB1-Pad47)") (class "Default")
      (node (ref "U1") (pin "47") (pinfunction "PB1_47") (pintype "passive"))
    )
    (net (code "167") (name "unconnected-(U1A-PB9-Pad140)") (class "Default")
      (node (ref "U1") (pin "140") (pinfunction "PB9_140") (pintype "passive"))
    )
    (net (code "168") (name "unconnected-(U1A-PB11-Pad70)") (class "Default")
      (node (ref "U1") (pin "70") (pinfunction "PB11_70") (pintype "passive"))
    )
    (net (code "169") (name "unconnected-(U1A-PC0-Pad26)") (class "Default")
      (node (ref "U1") (pin "26") (pinfunction "PC0_26") (pintype "passive"))
    )
    (net (code "170") (name "unconnected-(U1A-PC3-Pad29)") (class "Default")
      (node (ref "U1") (pin "29") (pinfunction "PC3_29") (pintype "passive"))
    )
    (net (code "171") (name "unconnected-(U1A-PC7-Pad97)") (class "Default")
      (node (ref "U1") (pin "97") (pinfunction "PC7_97") (pintype "passive"))
    )
    (net (code "172") (name "unconnected-(U1B-PD4-Pad118)") (class "Default")
      (node (ref "U1") (pin "118") (pinfunction "PD4_118") (pintype "passive"))
    )
    (net (code "173") (name "unconnected-(U1B-PE2-Pad1)") (class "Default")
      (node (ref "U1") (pin "1") (pinfunction "PE2_1") (pintype "passive"))
    )
    (net (code "174") (name "unconnected-(U1B-PE3-Pad2)") (class "Default")
      (node (ref "U1") (pin "2") (pinfunction "PE3_2") (pintype "passive"))
    )
    (net (code "175") (name "unconnected-(U1B-PE4-Pad3)") (class "Default")
      (node (ref "U1") (pin "3") (pinfunction "PE4_3") (pintype "passive"))
    )
    (net (code "176") (name "unconnected-(U1B-PE5-Pad4)") (class "Default")
      (node (ref "U1") (pin "4") (pinfunction "PE5_4") (pintype "passive"))
    )
    (net (code "177") (name "unconnected-(U1B-PE14-Pad67)") (class "Default")
      (node (ref "U1") (pin "67") (pinfunction "PE14_67") (pintype "passive"))
    )
    (net (code "178") (name "unconnected-(U1B-PF2-Pad12)") (class "Default")
      (node (ref "U1") (pin "12") (pinfunction "PF2_12") (pintype "passive"))
    )
    (net (code "179") (name "unconnected-(U1B-PF3-Pad13)") (class "Default")
      (node (ref "U1") (pin "13") (pinfunction "PF3_13") (pintype "passive"))
    )
    (net (code "180") (name "unconnected-(U1B-PF4-Pad14)") (class "Default")
      (node (ref "U1") (pin "14") (pinfunction "PF4_14") (pintype "passive"))
    )
    (net (code "181") (name "unconnected-(U1B-PF13-Pad53)") (class "Default")
      (node (ref "U1") (pin "53") (pinfunction "PF13_53") (pintype "passive"))
    )
    (net (code "182") (name "unconnected-(U1B-PG0-Pad56)") (class "Default")
      (node (ref "U1") (pin "56") (pinfunction "PG0_56") (pintype "passive"))
    )
    (net (code "183") (name "unconnected-(U1B-PG1-Pad57)") (class "Default")
      (node (ref "U1") (pin "57") (pinfunction "PG1_57") (pintype "passive"))
    )
    (net (code "184") (name "unconnected-(U4-NC-Pad1)") (class "Default")
      (node (ref "U4") (pin "1") (pinfunction "NC_1") (pintype "passive"))
    )
    (net (code "185") (name "unconnected-(U4-NC-Pad8)") (class "Default")
      (node (ref "U4") (pin "8") (pinfunction "NC_8") (pintype "passive"))
    )
    (net (code "186") (name "unconnected-(U12-CTS#-Pad9)") (class "Default")
      (node (ref "U12") (pin "9") (pinfunction "CTS#_9") (pintype "passive+no_connect"))
    )
    (net (code "187") (name "unconnected-(U12-DCD#-Pad12)") (class "Default")
      (node (ref "U12") (pin "12") (pinfunction "DCD#_12") (pintype "passive+no_connect"))
    )
    (net (code "188") (name "unconnected-(U12-DSR#-Pad10)") (class "Default")
      (node (ref "U12") (pin "10") (pinfunction "DSR#_10") (pintype "passive+no_connect"))
    )
    (net (code "189") (name "unconnected-(U12-DTR#-Pad13)") (class "Default")
      (node (ref "U12") (pin "13") (pinfunction "DTR#_13") (pintype "passive+no_connect"))
    )
    (net (code "190") (name "unconnected-(U12-NC-Pad8)") (class "Default")
      (node (ref "U12") (pin "8") (pinfunction "NC_8") (pintype "passive"))
    )
    (net (code "191") (name "unconnected-(U12-RI#-Pad11)") (class "Default")
      (node (ref "U12") (pin "11") (pinfunction "RI#_11") (pintype "passive+no_connect"))
    )
    (net (code "192") (name "unconnected-(U12-RTS#-Pad14)") (class "Default")
      (node (ref "U12") (pin "14") (pinfunction "RTS#_14") (pintype "passive+no_connect"))
    )
    (net (code "193") (name "unconnected-(U12-TNOW-Pad15)") (class "Default")
      (node (ref "U12") (pin "15") (pinfunction "TNOW_15") (pintype "passive+no_connect"))
    )
    (net (code "194") (name "unconnected-(U23-NC-Pad4)") (class "Default")
      (node (ref "U23") (pin "4") (pinfunction "NC_4") (pintype "passive"))
    )
    (net (code "195") (name "unconnected-(U23-VBUS-Pad1)") (class "Default")
      (node (ref "U23") (pin "1") (pinfunction "VBUS_1") (pintype "passive"))
    )
    (net (code "196") (name "unconnected-(U25-NC-Pad3)") (class "Default")
      (node (ref "U25") (pin "3") (pinfunction "NC_3") (pintype "passive"))
    )
    (net (code "197") (name "unconnected-(U25-NC-Pad4)") (class "Default")
      (node (ref "U25") (pin "4") (pinfunction "NC_4") (pintype "passive"))
    )
    (net (code "198") (name "unconnected-(U25-NC-Pad6)") (class "Default")
      (node (ref "U25") (pin "6") (pinfunction "NC_6") (pintype "passive"))
    )
    (net (code "199") (name "unconnected-(U25-NC-Pad7)") (class "Default")
      (node (ref "U25") (pin "7") (pinfunction "NC_7") (pintype "passive"))
    )
    (net (code "200") (name "unconnected-(U25-NC-Pad8)") (class "Default")
      (node (ref "U25") (pin "8") (pinfunction "NC_8") (pintype "passive"))
    )
    (net (code "201") (name "unconnected-(U25-NC-Pad9)") (class "Default")
      (node (ref "U25") (pin "9") (pinfunction "NC_9") (pintype "passive"))
    )
    (net (code "202") (name "unconnected-(U25-NC-Pad16)") (class "Default")
      (node (ref "U25") (pin "16") (pinfunction "NC_16") (pintype "passive"))
    )
    (net (code "203") (name "unconnected-(U25-NC-Pad18)") (class "Default")
      (node (ref "U25") (pin "18") (pinfunction "NC_18") (pintype "passive"))
    )
    (net (code "204") (name "unconnected-(U25-NC-Pad19)") (class "Default")
      (node (ref "U25") (pin "19") (pinfunction "NC_19") (pintype "passive"))
    )
    (net (code "205") (name "unconnected-(header1*6pin-Pad3)") (class "Default")
      (node (ref "header1*6pin") (pin "3") (pinfunction "3_3") (pintype "passive"))
    )
  )
)
